# PCB_Plate_v6.net
KiCad netlist of a schematic drawn in EAGLE
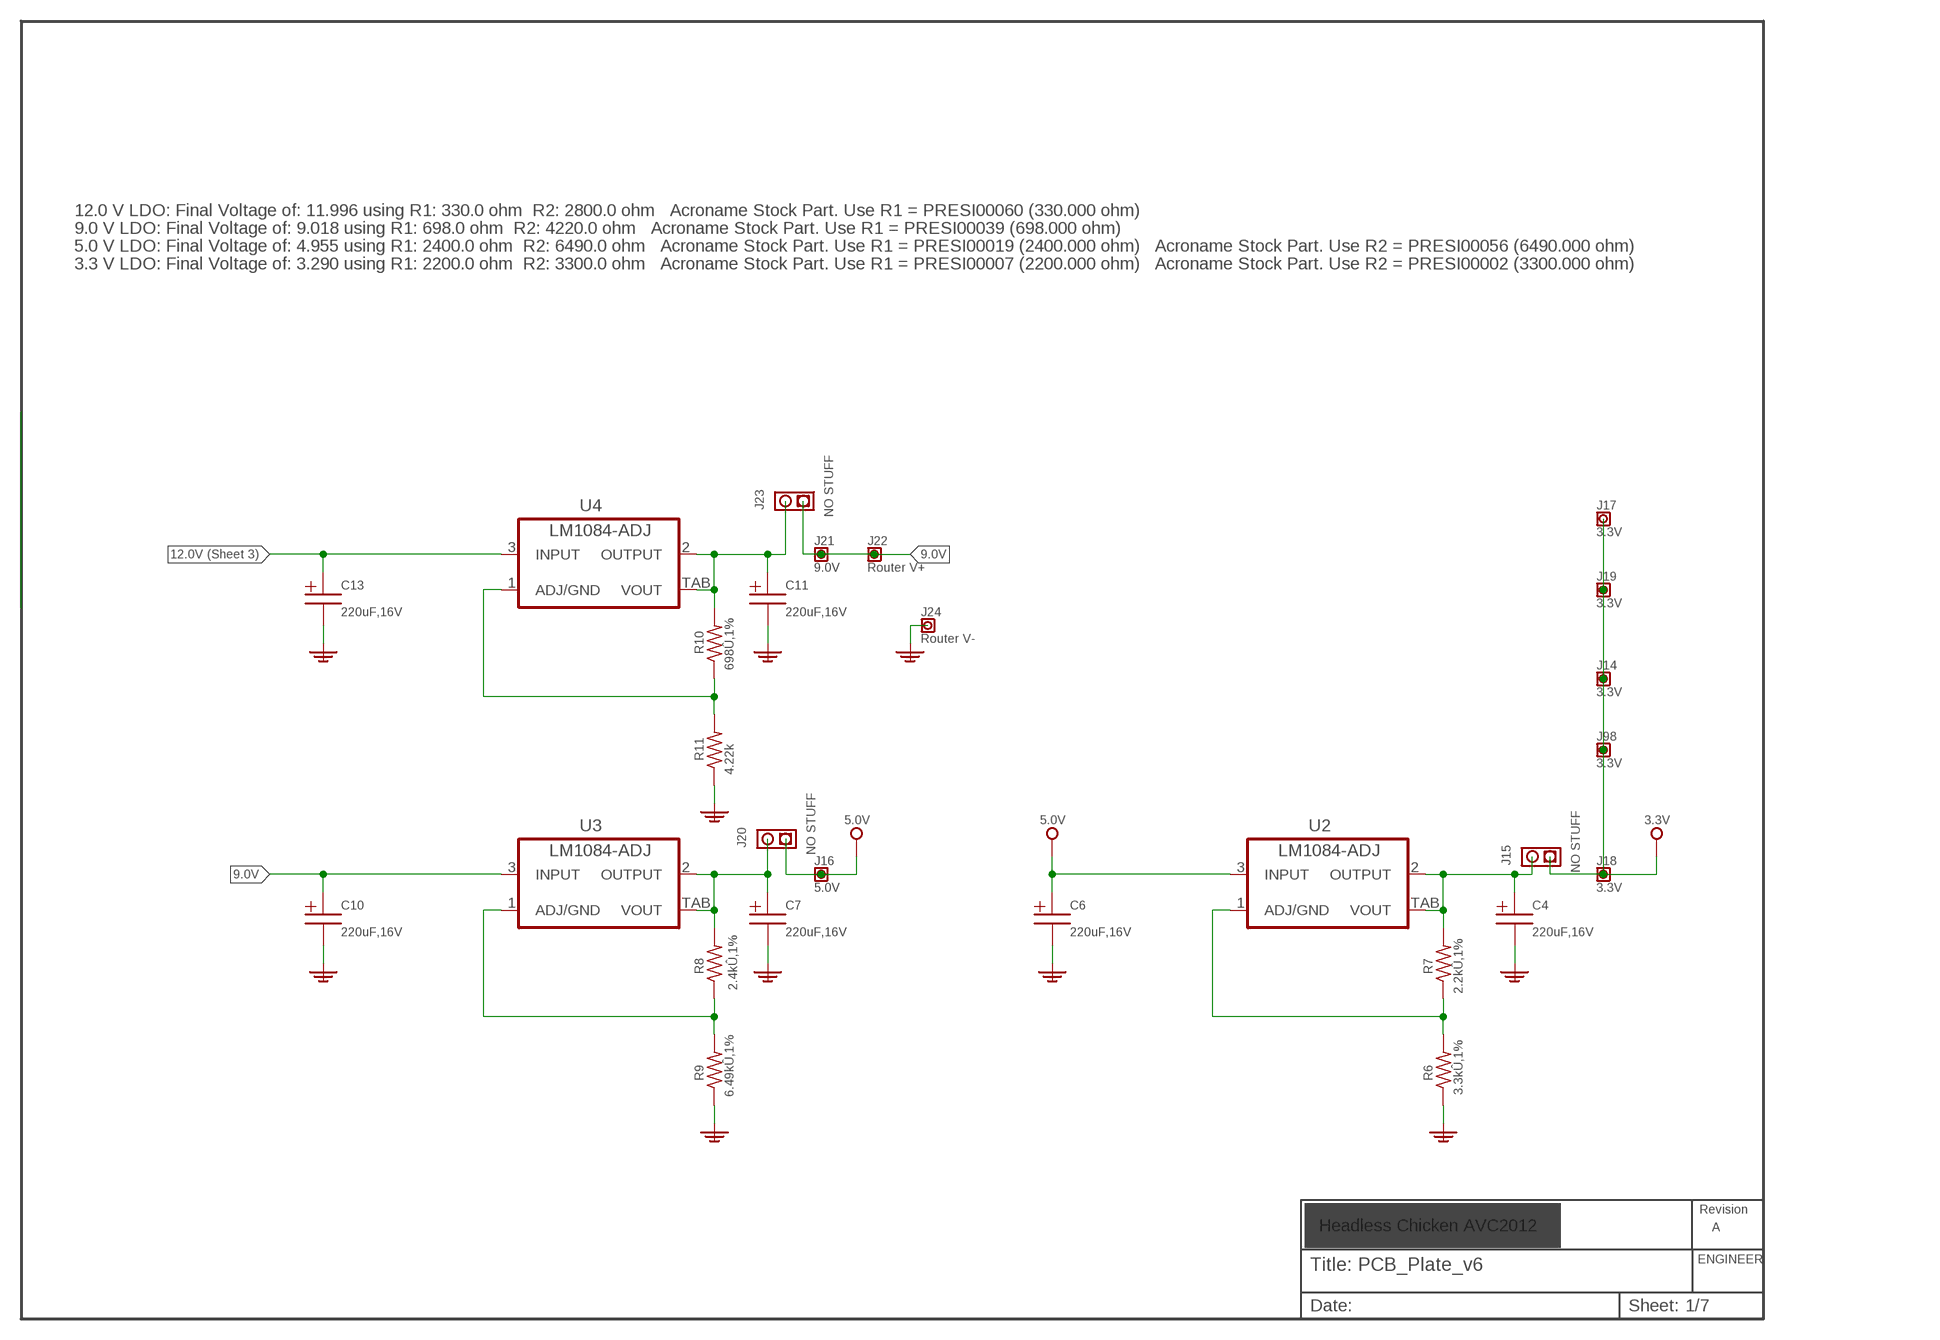
[diagram p0: schematic, sheet 1]
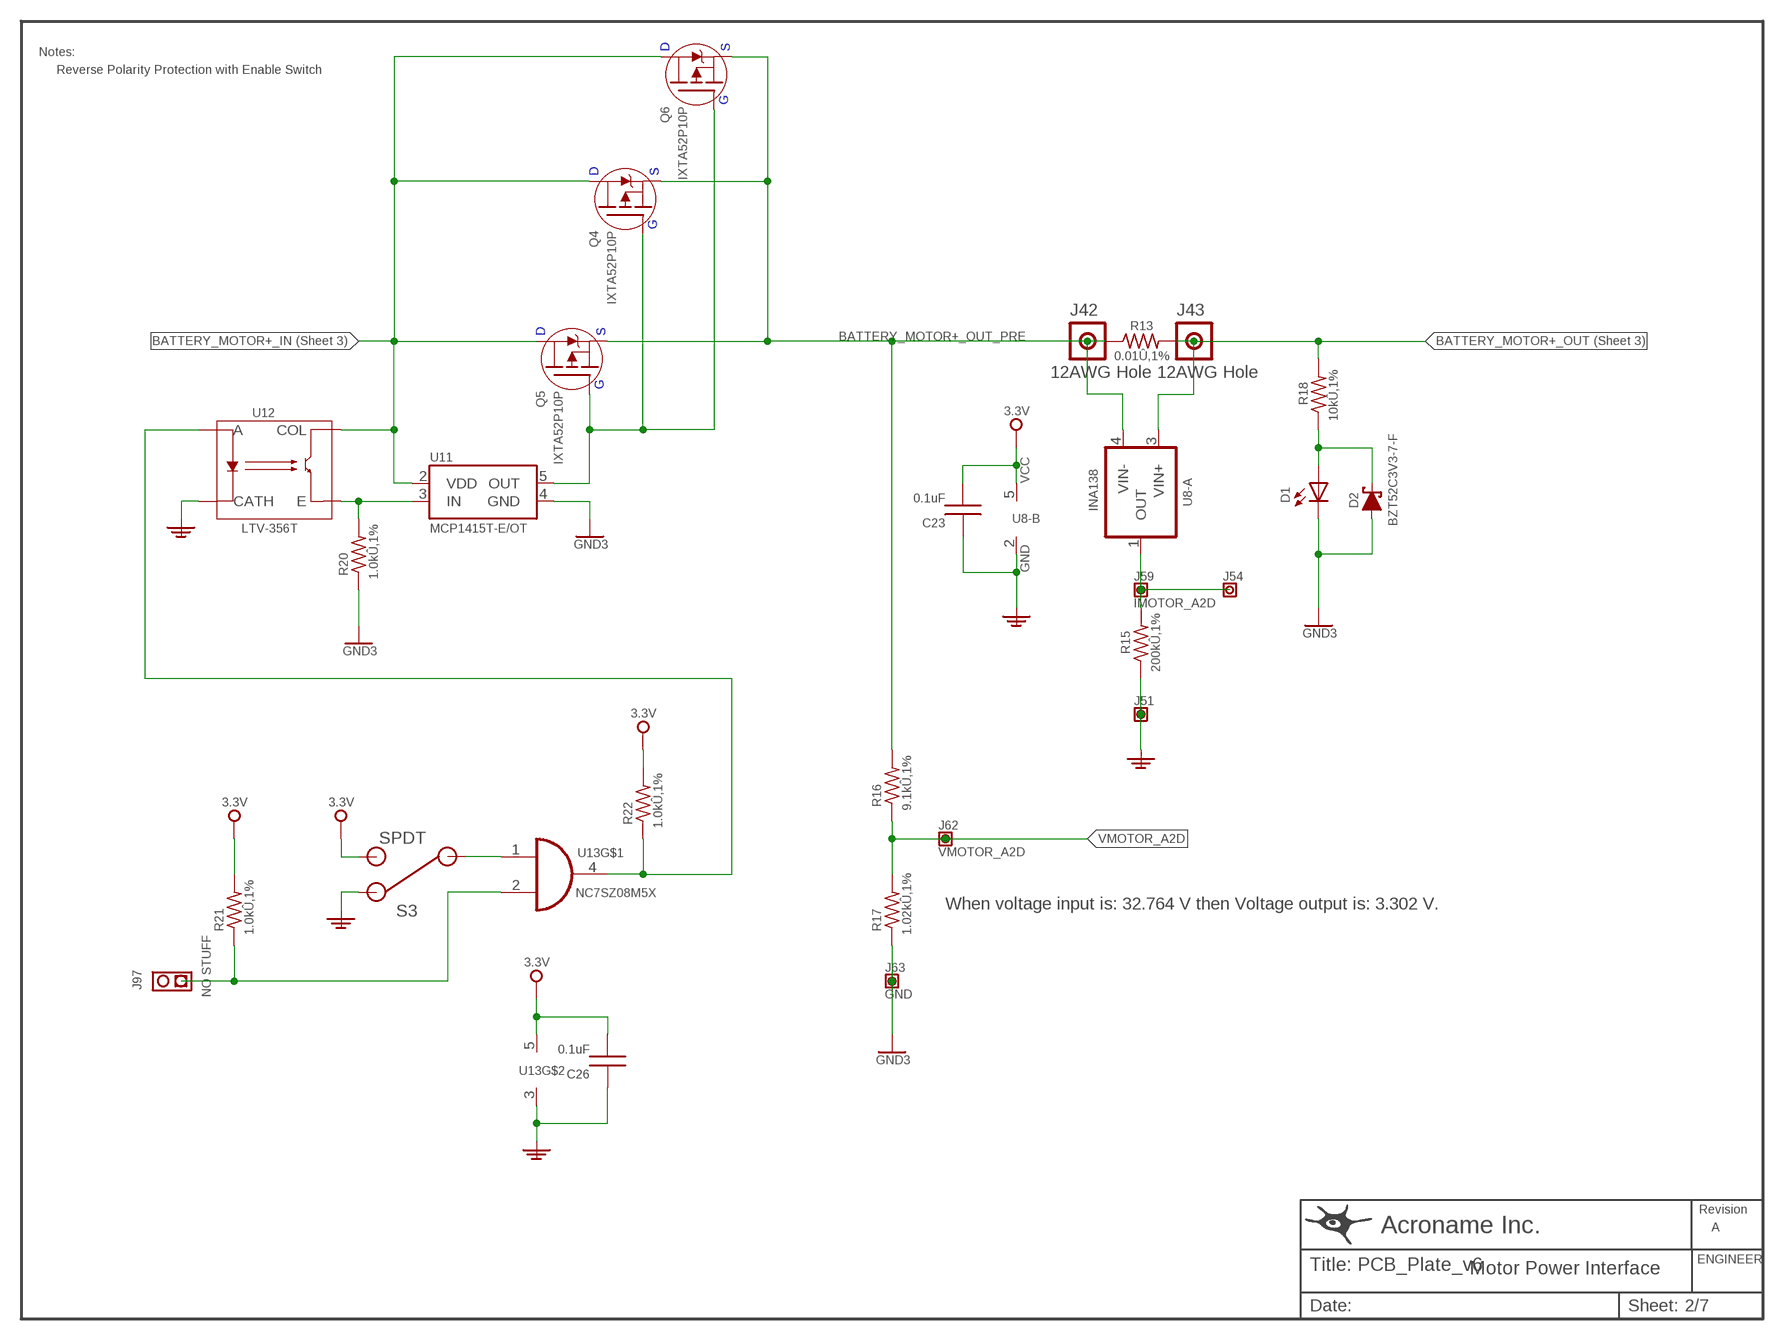
[diagram p1: schematic, sheet 2]
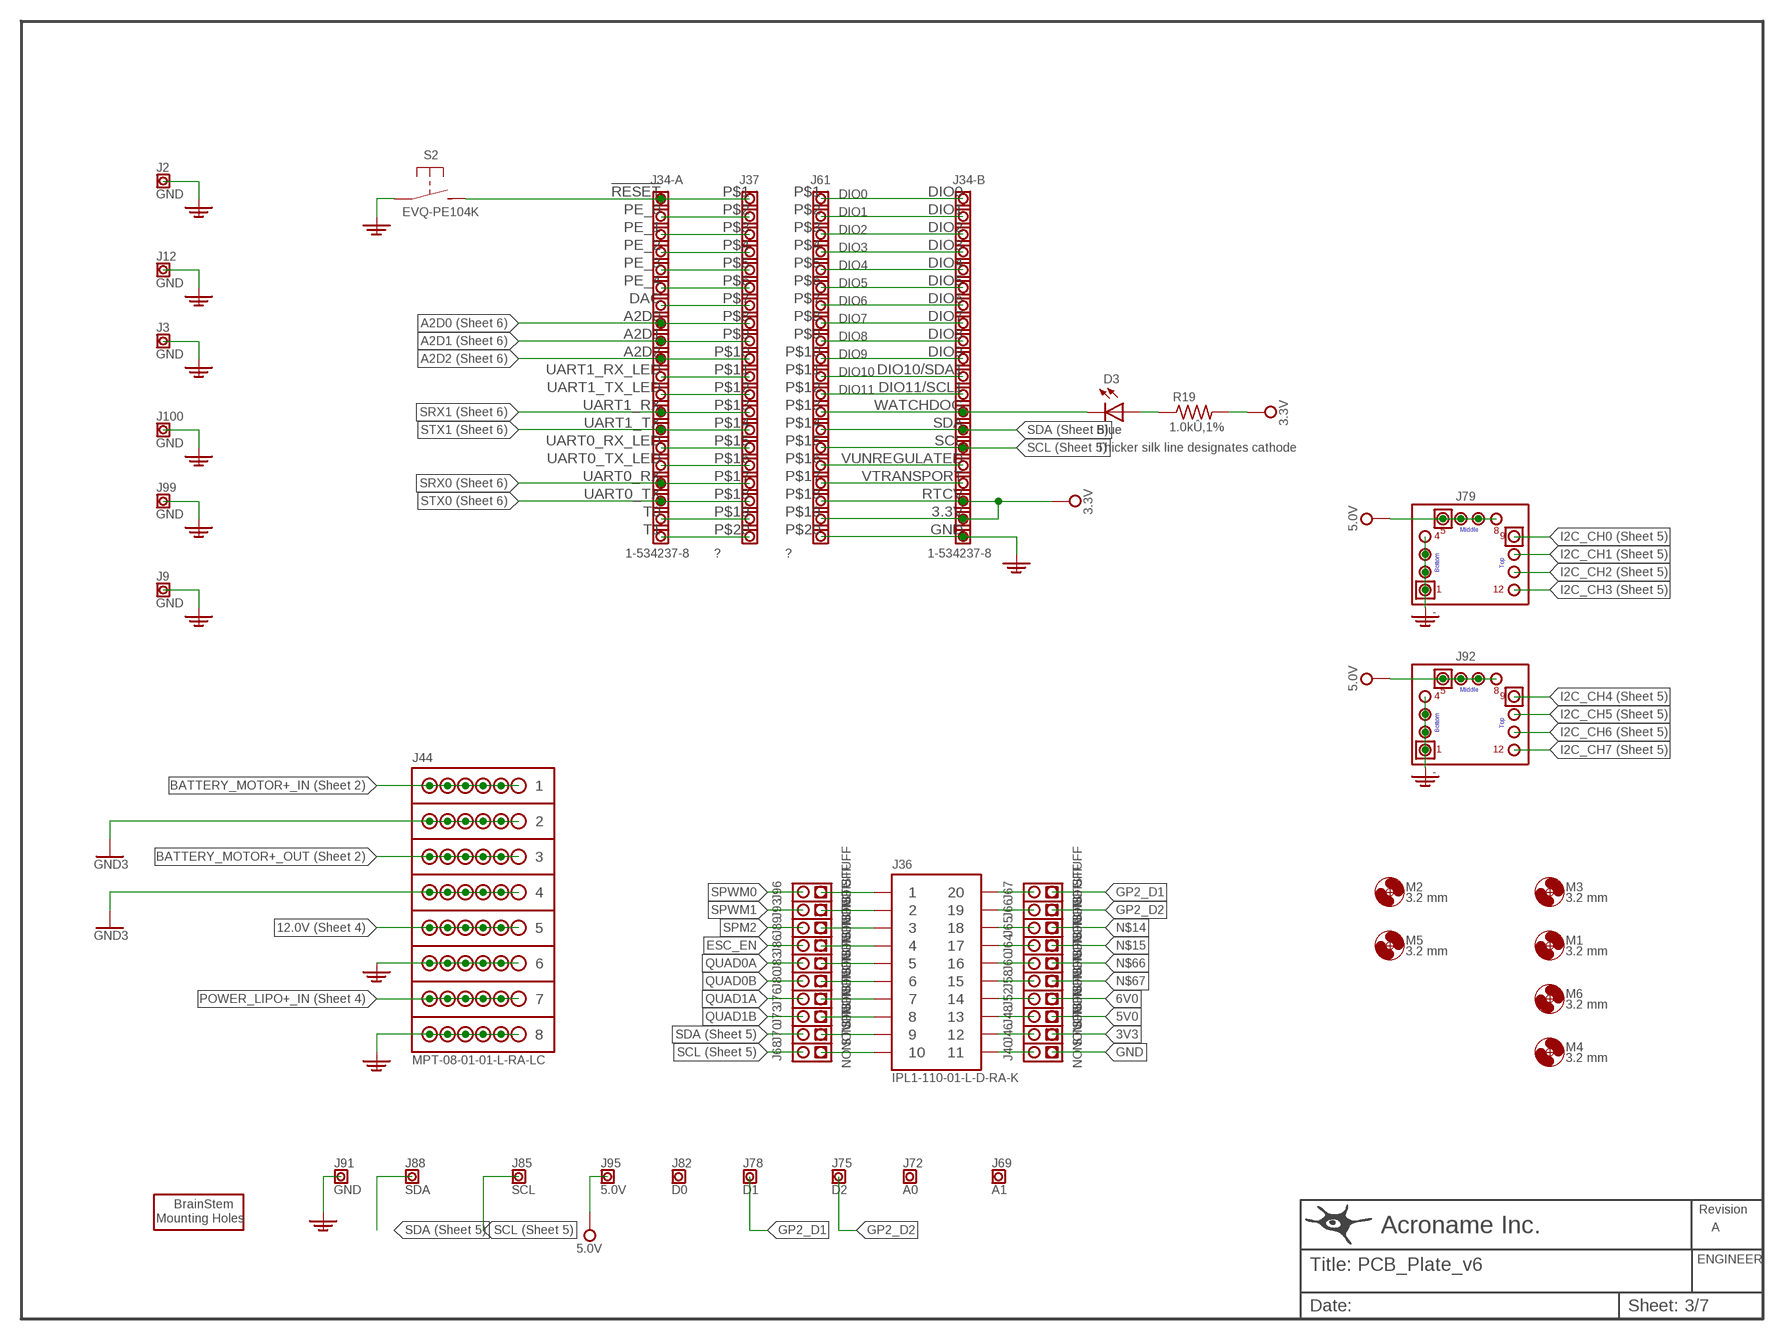
[diagram p2: schematic, sheet 3]
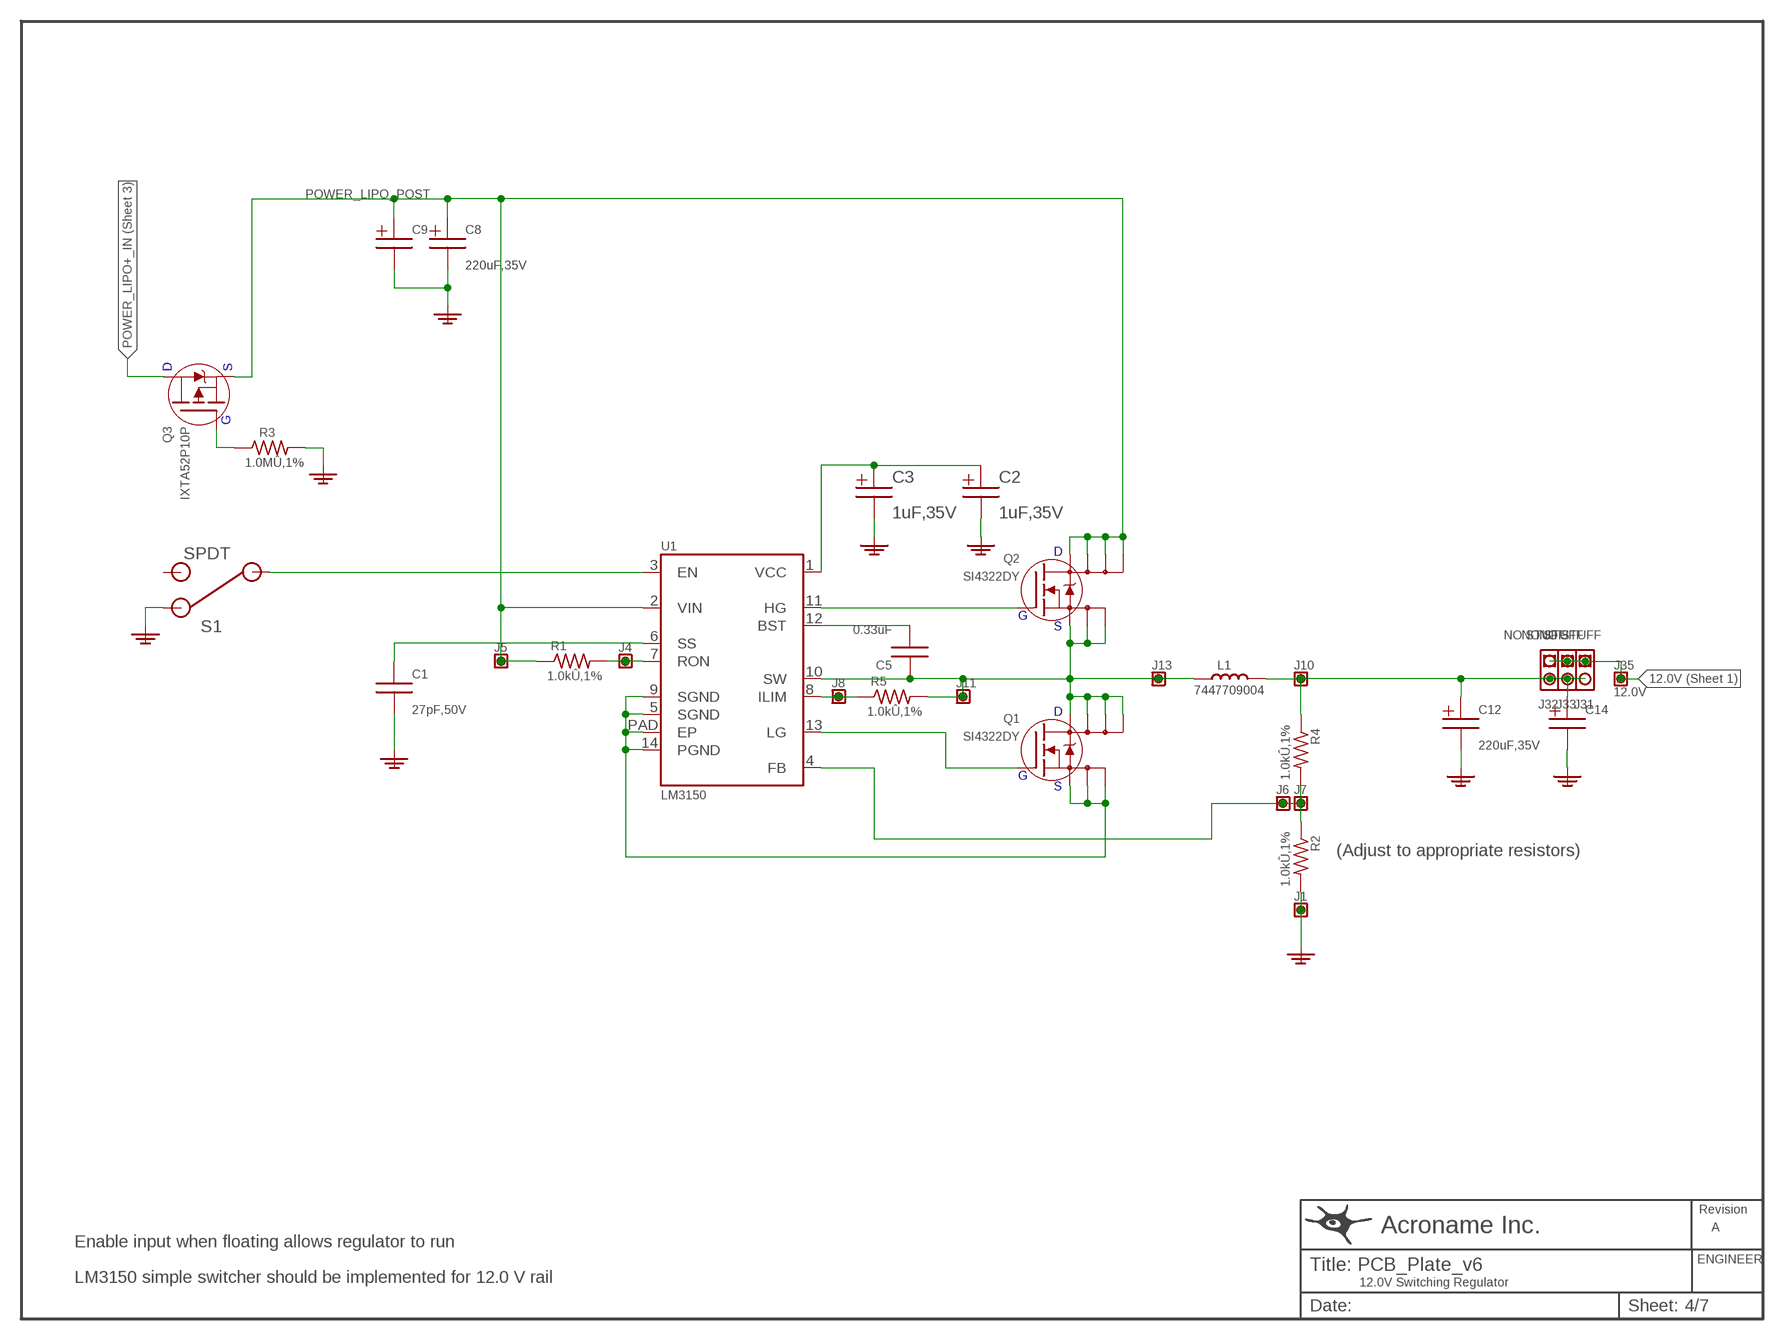
[diagram p3: schematic, sheet 4]
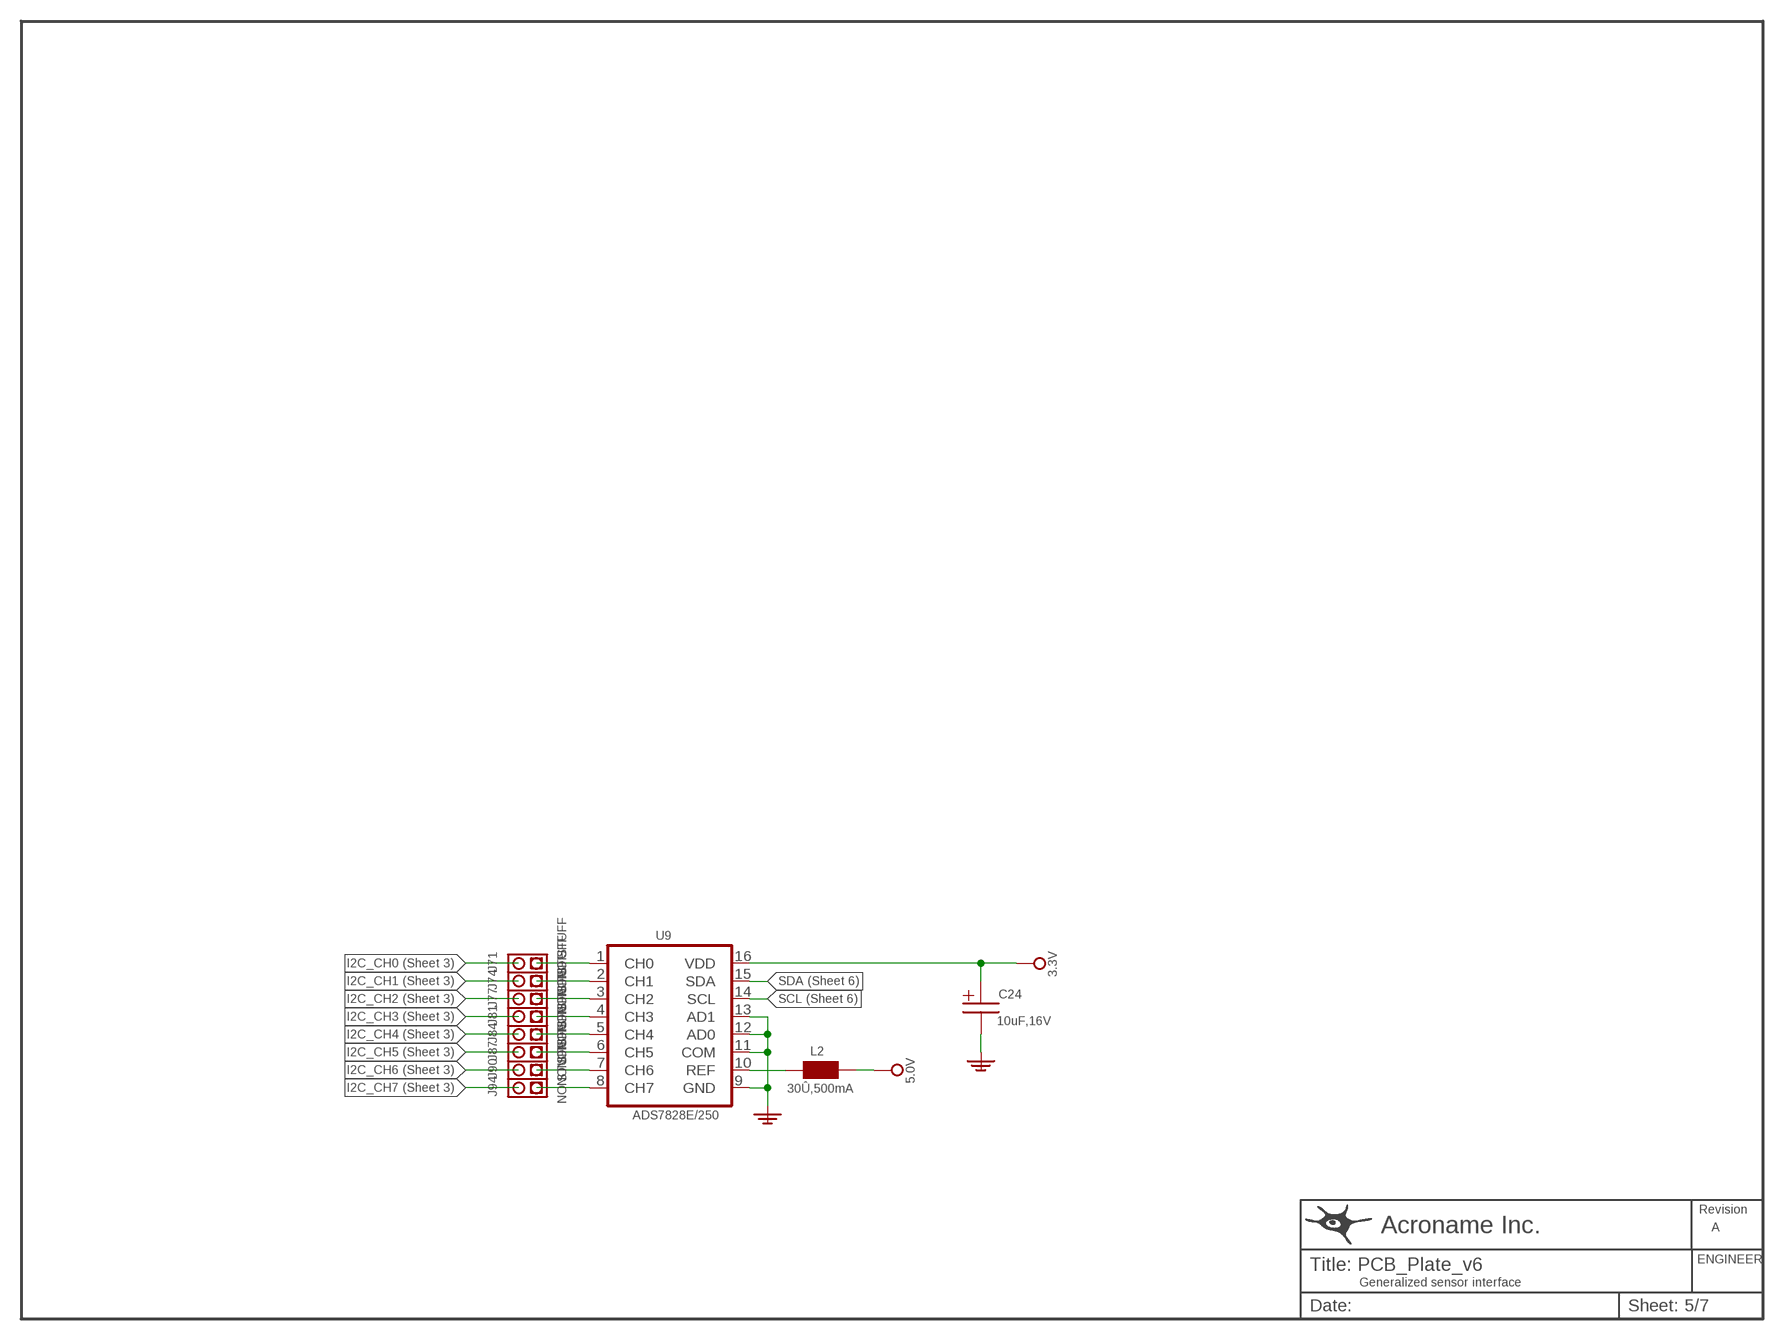
[diagram p4: schematic, sheet 5]
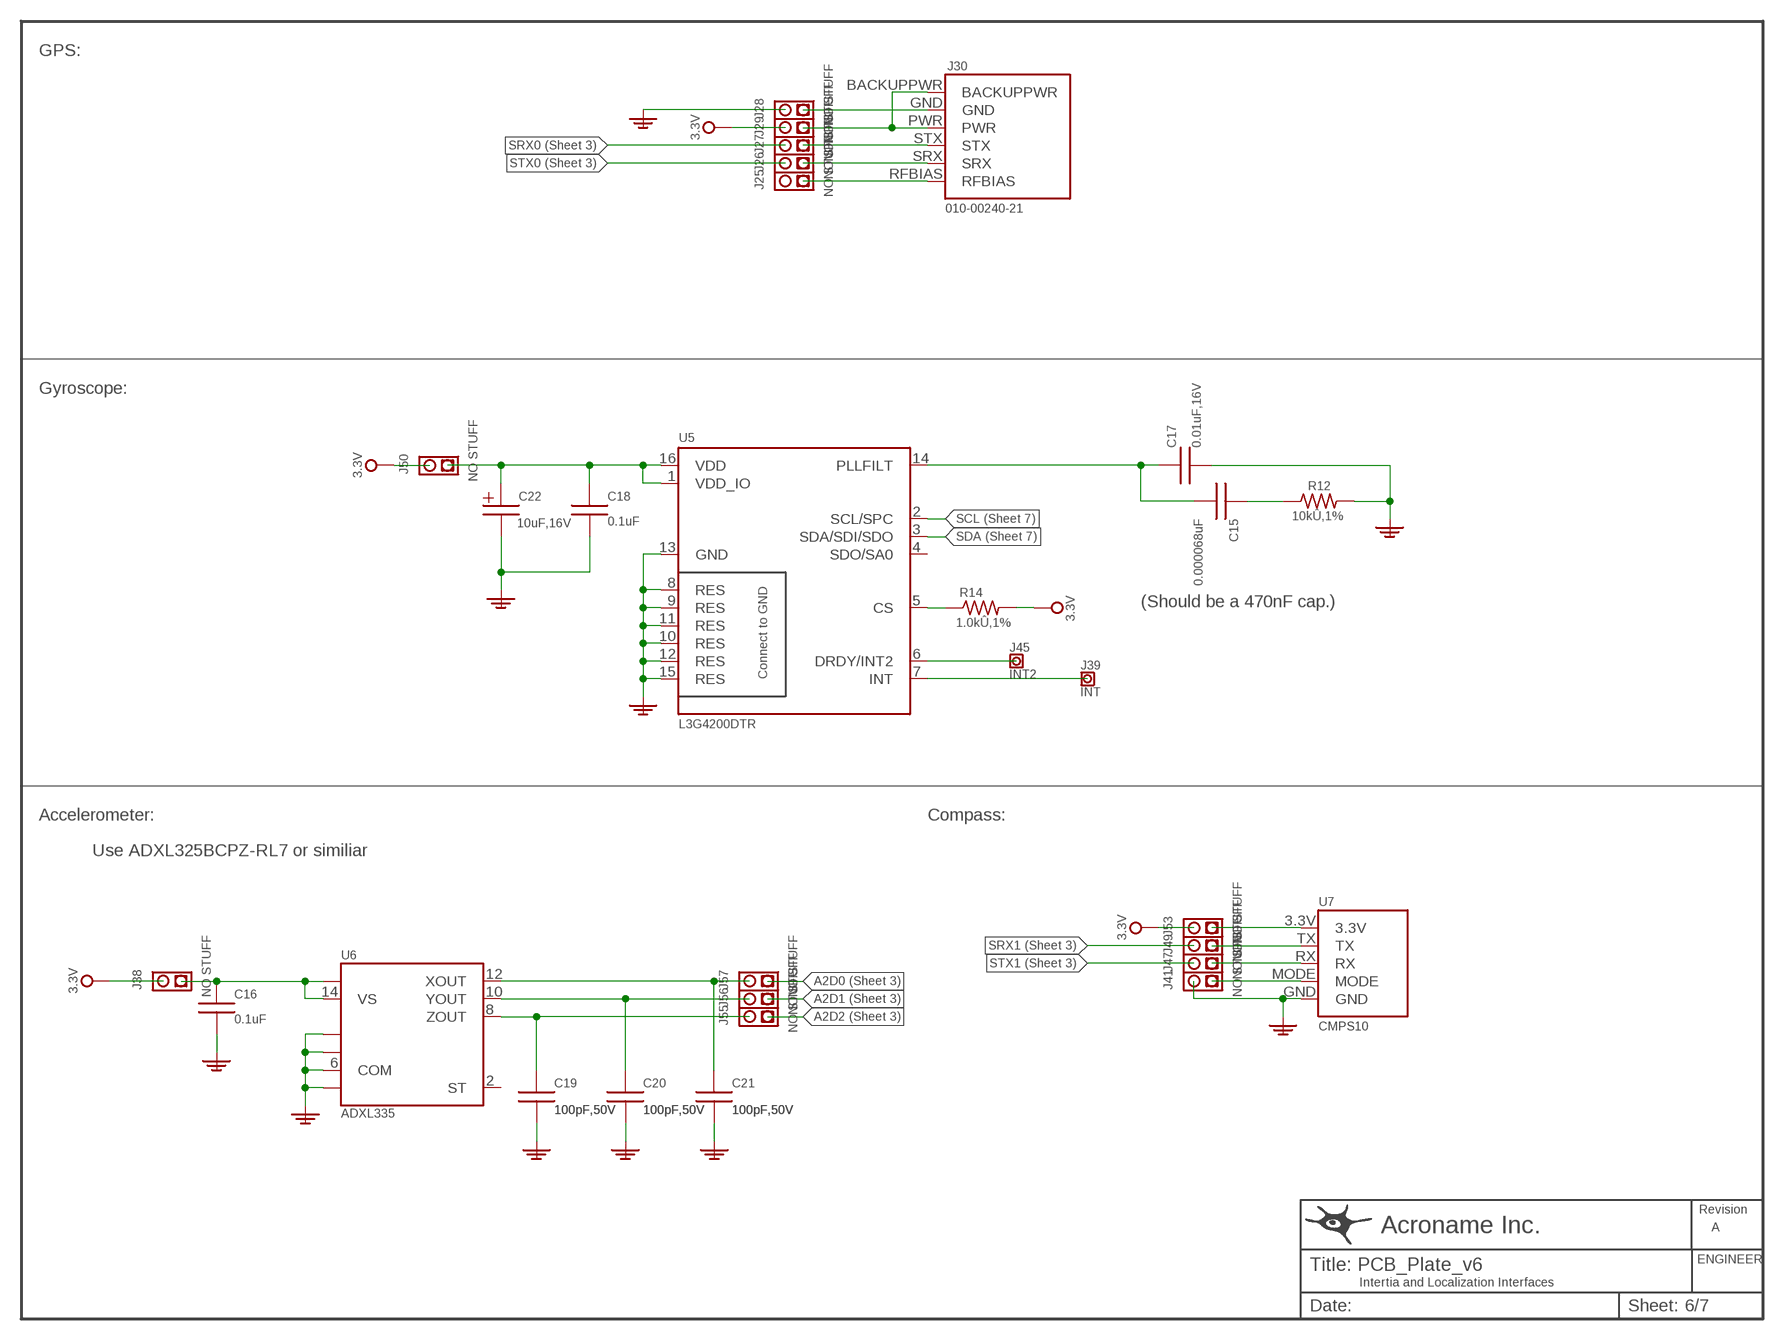
[diagram p5: schematic, sheet 6]
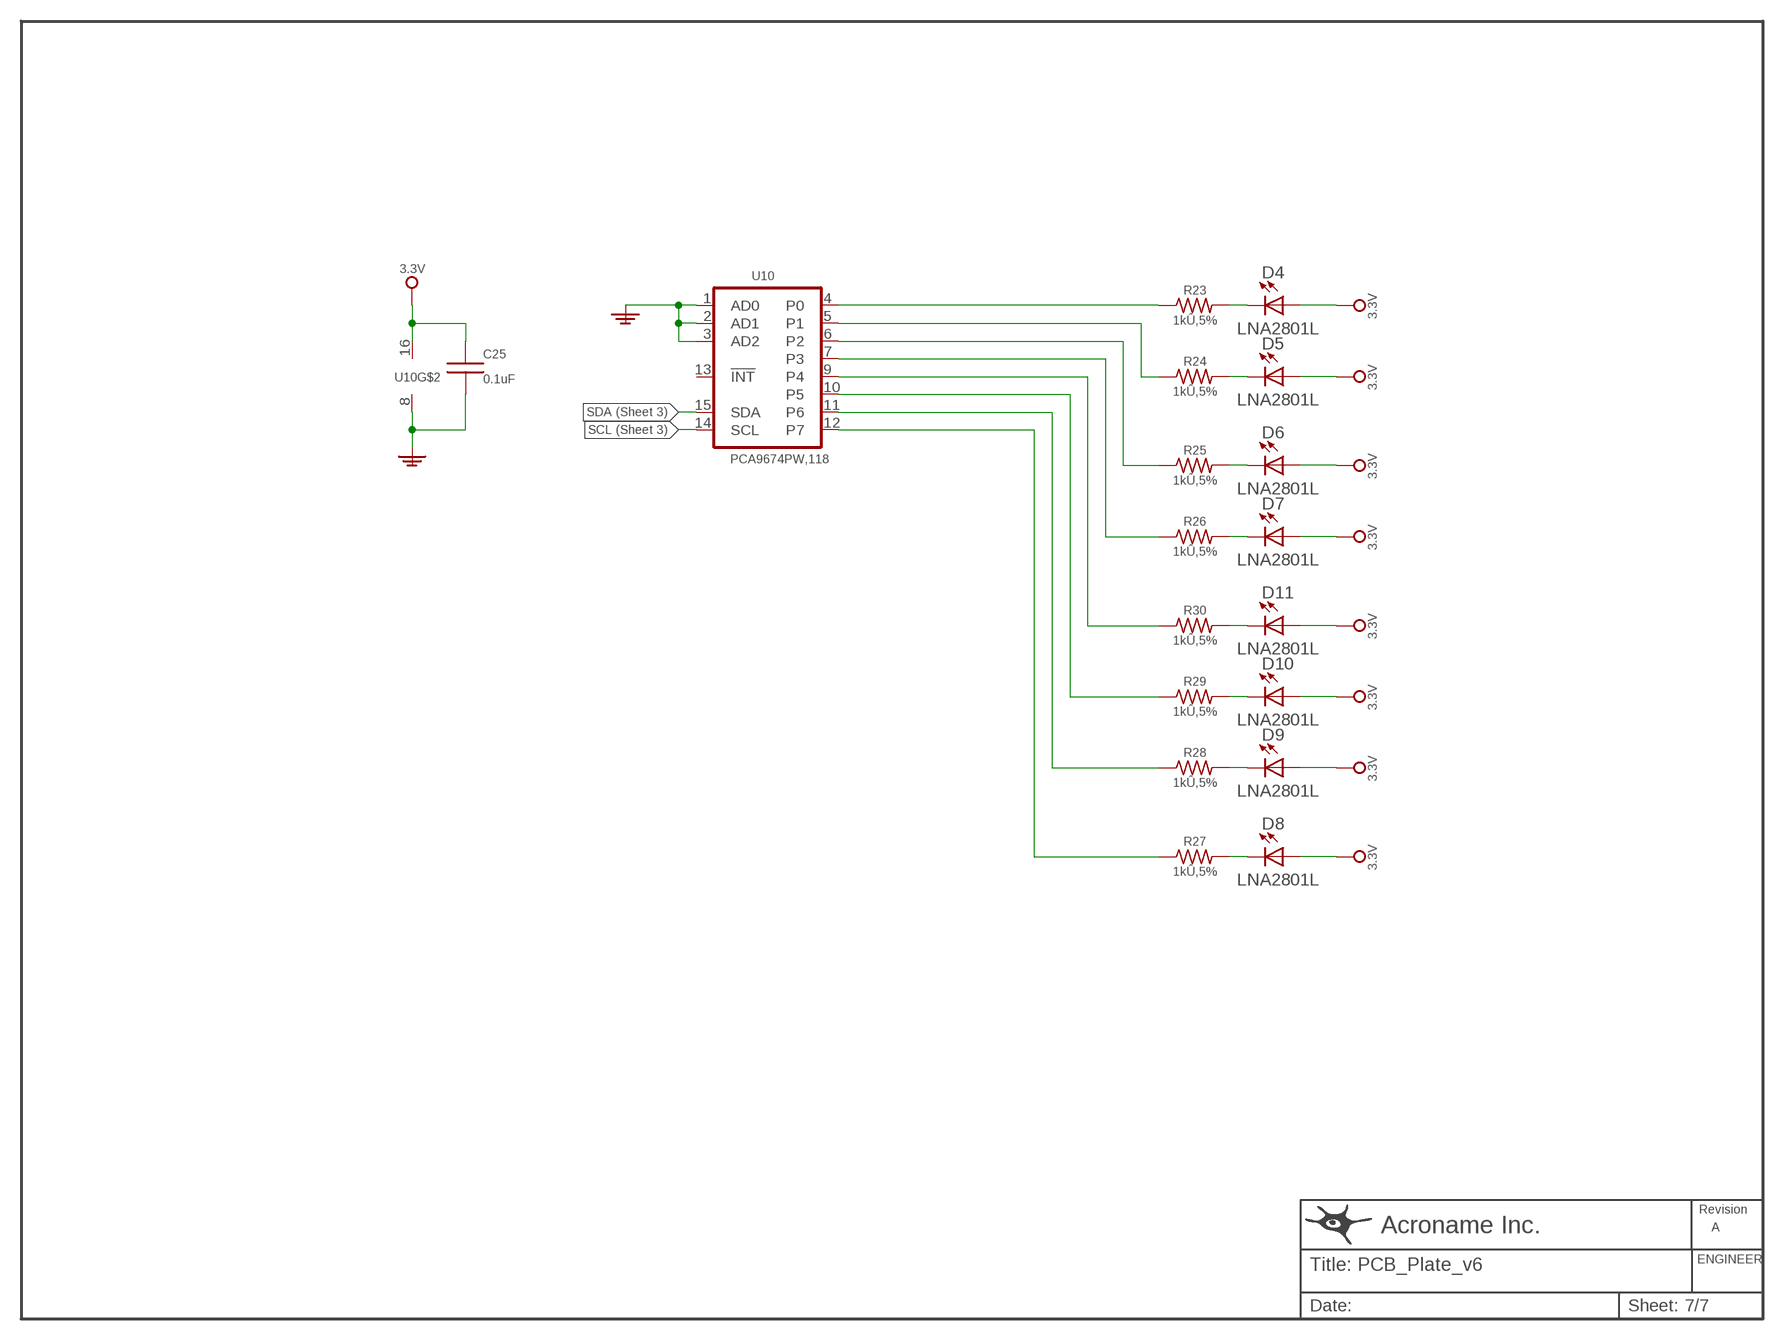
[diagram p6: schematic, sheet 7]

(export (version "E")
  (design (tool "Eeschema 10.0.6"))
  (components
    (comp (ref "C23")
      (value "PCAPI00015")
      (footprint "eagle-import:C0603")
      (fields (field (name "PARTNUM") "ECJ-1VB1E104K"))
      (libsource (lib "eagle-import") (part "PCAPI00015"))
    )
    (comp (ref "C26")
      (value "PCAPI00015")
      (footprint "eagle-import:C0603")
      (fields
        (field (name "PARTNUM") "ECJ-1VB1E104K")
        (field (name "ACRONAME") "PCAPI00015")
        (field (name "PARTNUM_1") "ECJ-1VB1E104K")
      )
      (libsource (lib "eagle-import") (part "PCAPI00015"))
    )
    (comp (ref "D1")
      (value "PDIOD00001")
      (footprint "eagle-import:CHIPLED_0805")
      (fields (field (name "PARTNUM") "LTST-C171CKT"))
      (libsource (lib "eagle-import") (part "PDIOD00001"))
    )
    (comp (ref "D2")
      (value "BZT52C3V3-7-F")
      (footprint "eagle-import:SOD123")
      (libsource (lib "eagle-import") (part "BZT52C3V3-7-F"))
    )
    (comp (ref "J42")
      (value "BOARD00008")
      (footprint "eagle-import:TSW1X1_12AWG")
      (libsource (lib "eagle-import") (part "BOARD00008"))
    )
    (comp (ref "J43")
      (value "BOARD00008")
      (footprint "eagle-import:TSW1X1_12AWG")
      (libsource (lib "eagle-import") (part "BOARD00008"))
    )
    (comp (ref "J51")
      (value "BOARD00003WVALUE")
      (footprint "eagle-import:TSW1X1_VAL")
      (libsource (lib "eagle-import") (part "BOARD00003WVALUE"))
    )
    (comp (ref "J54")
      (value "BOARD00003WVALUE")
      (footprint "eagle-import:TSW1X1_VAL")
      (libsource (lib "eagle-import") (part "BOARD00003WVALUE"))
    )
    (comp (ref "J59")
      (value "IMOTOR_A2D")
      (footprint "eagle-import:TSW1X1_VAL")
      (libsource (lib "eagle-import") (part "BOARD00003WVALUE"))
    )
    (comp (ref "J62")
      (value "VMOTOR_A2D")
      (footprint "eagle-import:TSW1X1_VAL")
      (libsource (lib "eagle-import") (part "BOARD00003WVALUE"))
    )
    (comp (ref "J63")
      (value "GND")
      (footprint "eagle-import:TSW1X1_VAL")
      (libsource (lib "eagle-import") (part "BOARD00003WVALUE"))
    )
    (comp (ref "J97")
      (value "BOARD00012")
      (footprint "eagle-import:TSW1X2")
      (libsource (lib "eagle-import") (part "BOARD00012"))
    )
    (comp (ref "Q4")
      (value "IXTA52P10P")
      (footprint "eagle-import:D2PACK")
      (fields (field (name "NOTES") "No Stuff"))
      (libsource (lib "eagle-import") (part "IXTA52P10P"))
    )
    (comp (ref "Q5")
      (value "IXTA52P10P")
      (footprint "eagle-import:D2PACK")
      (libsource (lib "eagle-import") (part "IXTA52P10P"))
    )
    (comp (ref "Q6")
      (value "IXTA52P10P")
      (footprint "eagle-import:D2PACK")
      (fields (field (name "NOTES") "No Stuff"))
      (libsource (lib "eagle-import") (part "IXTA52P10P"))
    )
    (comp (ref "R13")
      (value "PRESI00041")
      (footprint "eagle-import:R4527")
      (fields (field (name "PARTNUM") "WSR5R0100FEA"))
      (libsource (lib "eagle-import") (part "PRESI00041"))
    )
    (comp (ref "R15")
      (value "PRESI00018")
      (footprint "eagle-import:R0603")
      (libsource (lib "eagle-import") (part "PRESI00018"))
    )
    (comp (ref "R16")
      (value "ERJ-2RKF9101X")
      (footprint "eagle-import:R0402@1")
      (libsource (lib "eagle-import") (part "ERJ-2RKF9101X"))
    )
    (comp (ref "R17")
      (value "ERJ-2RKF1021X")
      (footprint "eagle-import:R0402@1")
      (libsource (lib "eagle-import") (part "ERJ-2RKF1021X"))
    )
    (comp (ref "R18")
      (value "PRESI00005")
      (footprint "eagle-import:R0603")
      (fields (field (name "PARTNUM") "ERJ-3EKF1002V"))
      (libsource (lib "eagle-import") (part "PRESI00005"))
    )
    (comp (ref "R20")
      (value "PRESI00006")
      (footprint "eagle-import:R0603")
      (fields
        (field (name "PARTNUM") "ERJ-3EKF1001V")
        (field (name "ACRONAME") "PRESI00006")
        (field (name "PARTNUM_1") "ERJ-3EKF1001V")
        (field (name "UNITCOST") "0.006")
      )
      (libsource (lib "eagle-import") (part "PRESI00006"))
    )
    (comp (ref "R21")
      (value "PRESI00006")
      (footprint "eagle-import:R0603")
      (fields
        (field (name "PARTNUM") "ERJ-3EKF1001V")
        (field (name "ACRONAME") "PRESI00006")
        (field (name "PARTNUM_1") "ERJ-3EKF1001V")
        (field (name "UNITCOST") "0.006")
      )
      (libsource (lib "eagle-import") (part "PRESI00006"))
    )
    (comp (ref "R22")
      (value "PRESI00006")
      (footprint "eagle-import:R0603")
      (fields (field (name "PARTNUM") "ERJ-3EKF1001V"))
      (libsource (lib "eagle-import") (part "PRESI00006"))
    )
    (comp (ref "S3")
      (value "PMISC00005")
      (footprint "eagle-import:SPDTRA")
      (fields (field (name "PARTNUM") "1101M2S3AQE2"))
      (libsource (lib "eagle-import") (part "PMISC00005"))
    )
    (comp (ref "U8")
      (value "PCHIP00026")
      (footprint "eagle-import:SOT23-5")
      (fields (field (name "PARTNUM") "INA168NA/250"))
      (libsource (lib "eagle-import") (part "PCHIP00026"))
    )
    (comp (ref "U11")
      (value "MCP1416")
      (footprint "eagle-import:SOT23-5")
      (fields (field (name "PARTNUM") "MCP1416T-E/OT") (field (name "PARTNUM_1") "MCP1415T-E/OT"))
      (libsource (lib "eagle-import") (part "MCP1416"))
    )
    (comp (ref "U12")
      (value "LTV-356T")
      (footprint "eagle-import:4-SMD")
      (libsource (lib "eagle-import") (part "LTV-356T"))
    )
    (comp (ref "U13")
      (value "NC7SZ08M5X")
      (footprint "eagle-import:SOT23-5")
      (libsource (lib "eagle-import") (part "NC7SZ08M5X"))
    )
    (comp (ref "C25")
      (value "PCAPI00015")
      (footprint "eagle-import:C0603")
      (fields (field (name "PARTNUM") "ECJ-1VB1E104K"))
      (libsource (lib "eagle-import") (part "PCAPI00015"))
    )
    (comp (ref "D4")
      (value "PDIOD00003")
      (footprint "eagle-import:LT3LR1N02-001")
      (libsource (lib "eagle-import") (part "PDIOD00003"))
    )
    (comp (ref "D5")
      (value "PDIOD00003")
      (footprint "eagle-import:LT3LR1N02-001")
      (libsource (lib "eagle-import") (part "PDIOD00003"))
    )
    (comp (ref "D6")
      (value "PDIOD00003")
      (footprint "eagle-import:LT3LR1N02-001")
      (libsource (lib "eagle-import") (part "PDIOD00003"))
    )
    (comp (ref "D7")
      (value "PDIOD00003")
      (footprint "eagle-import:LT3LR1N02-001")
      (libsource (lib "eagle-import") (part "PDIOD00003"))
    )
    (comp (ref "D8")
      (value "PDIOD00003")
      (footprint "eagle-import:LT3LR1N02-001")
      (libsource (lib "eagle-import") (part "PDIOD00003"))
    )
    (comp (ref "D9")
      (value "PDIOD00003")
      (footprint "eagle-import:LT3LR1N02-001")
      (libsource (lib "eagle-import") (part "PDIOD00003"))
    )
    (comp (ref "D10")
      (value "PDIOD00003")
      (footprint "eagle-import:LT3LR1N02-001")
      (libsource (lib "eagle-import") (part "PDIOD00003"))
    )
    (comp (ref "D11")
      (value "PDIOD00003")
      (footprint "eagle-import:LT3LR1N02-001")
      (libsource (lib "eagle-import") (part "PDIOD00003"))
    )
    (comp (ref "R23")
      (value "PRESI00012")
      (footprint "eagle-import:CFR-12")
      (fields (field (name "PARTNUM") "?"))
      (libsource (lib "eagle-import") (part "PRESI00012"))
    )
    (comp (ref "R24")
      (value "PRESI00012")
      (footprint "eagle-import:CFR-12")
      (fields (field (name "PARTNUM") "?"))
      (libsource (lib "eagle-import") (part "PRESI00012"))
    )
    (comp (ref "R25")
      (value "PRESI00012")
      (footprint "eagle-import:CFR-12")
      (fields (field (name "PARTNUM") "?"))
      (libsource (lib "eagle-import") (part "PRESI00012"))
    )
    (comp (ref "R26")
      (value "PRESI00012")
      (footprint "eagle-import:CFR-12")
      (fields (field (name "PARTNUM") "?"))
      (libsource (lib "eagle-import") (part "PRESI00012"))
    )
    (comp (ref "R27")
      (value "PRESI00012")
      (footprint "eagle-import:CFR-12")
      (fields (field (name "PARTNUM") "?"))
      (libsource (lib "eagle-import") (part "PRESI00012"))
    )
    (comp (ref "R28")
      (value "PRESI00012")
      (footprint "eagle-import:CFR-12")
      (fields (field (name "PARTNUM") "?"))
      (libsource (lib "eagle-import") (part "PRESI00012"))
    )
    (comp (ref "R29")
      (value "PRESI00012")
      (footprint "eagle-import:CFR-12")
      (fields (field (name "PARTNUM") "?"))
      (libsource (lib "eagle-import") (part "PRESI00012"))
    )
    (comp (ref "R30")
      (value "PRESI00012")
      (footprint "eagle-import:CFR-12")
      (fields (field (name "PARTNUM") "?"))
      (libsource (lib "eagle-import") (part "PRESI00012"))
    )
    (comp (ref "U10")
      (value "I2C_DIO_EXPANDER")
      (footprint "eagle-import:TSSOP16")
      (fields (field (name "PARTNUM") "PCA9674PW,118"))
      (libsource (lib "eagle-import") (part "I2C_DIO_EXPANDER"))
    )
    (comp (ref "C15")
      (value "PCAPI00023")
      (footprint "eagle-import:C0603")
      (libsource (lib "eagle-import") (part "PCAPI00023"))
    )
    (comp (ref "C16")
      (value "PCAPI00015")
      (footprint "eagle-import:C0603")
      (fields (field (name "PARTNUM") "ECJ-1VB1E104K"))
      (libsource (lib "eagle-import") (part "PCAPI00015"))
    )
    (comp (ref "C17")
      (value "PCAPI00007")
      (footprint "eagle-import:C0603")
      (fields (field (name "PARTNUM") "ECJ-1VB1C103K"))
      (libsource (lib "eagle-import") (part "PCAPI00007"))
    )
    (comp (ref "C18")
      (value "PCAPI00015")
      (footprint "eagle-import:C0603")
      (fields (field (name "PARTNUM") "ECJ-1VB1E104K"))
      (libsource (lib "eagle-import") (part "PCAPI00015"))
    )
    (comp (ref "C19")
      (value "PCAPI00016")
      (footprint "eagle-import:C0603")
      (fields (field (name "PARTNUM") "ECJ-1VC1H101J"))
      (libsource (lib "eagle-import") (part "PCAPI00016"))
    )
    (comp (ref "C20")
      (value "PCAPI00016")
      (footprint "eagle-import:C0603")
      (fields (field (name "PARTNUM") "ECJ-1VC1H101J"))
      (libsource (lib "eagle-import") (part "PCAPI00016"))
    )
    (comp (ref "C21")
      (value "PCAPI00016")
      (footprint "eagle-import:C0603")
      (fields (field (name "PARTNUM") "ECJ-1VC1H101J"))
      (libsource (lib "eagle-import") (part "PCAPI00016"))
    )
    (comp (ref "C22")
      (value "T491A106K010AT")
      (footprint "eagle-import:SMC_A")
      (fields (field (name "PARTNUM") "T491A106M016AT"))
      (libsource (lib "eagle-import") (part "T491A106K010AT"))
    )
    (comp (ref "J25")
      (value "BOARD00012")
      (footprint "eagle-import:TSW1X2")
      (libsource (lib "eagle-import") (part "BOARD00012"))
    )
    (comp (ref "J26")
      (value "BOARD00012")
      (footprint "eagle-import:TSW1X2")
      (libsource (lib "eagle-import") (part "BOARD00012"))
    )
    (comp (ref "J27")
      (value "BOARD00012")
      (footprint "eagle-import:TSW1X2")
      (libsource (lib "eagle-import") (part "BOARD00012"))
    )
    (comp (ref "J28")
      (value "BOARD00012")
      (footprint "eagle-import:TSW1X2")
      (libsource (lib "eagle-import") (part "BOARD00012"))
    )
    (comp (ref "J29")
      (value "BOARD00012")
      (footprint "eagle-import:TSW1X2")
      (libsource (lib "eagle-import") (part "BOARD00012"))
    )
    (comp (ref "J30")
      (value "GPS15X")
      (footprint "eagle-import:GPS15")
      (fields (field (name "PARTNUM") "010-00240-21 "))
      (libsource (lib "eagle-import") (part "GPS15X"))
    )
    (comp (ref "J38")
      (value "BOARD00012")
      (footprint "eagle-import:TSW1X2")
      (libsource (lib "eagle-import") (part "BOARD00012"))
    )
    (comp (ref "J39")
      (value "INT")
      (footprint "eagle-import:TSW1X1_VAL")
      (libsource (lib "eagle-import") (part "BOARD00003WVALUE"))
    )
    (comp (ref "J41")
      (value "BOARD00012")
      (footprint "eagle-import:TSW1X2")
      (libsource (lib "eagle-import") (part "BOARD00012"))
    )
    (comp (ref "J45")
      (value "INT2")
      (footprint "eagle-import:TSW1X1_VAL")
      (libsource (lib "eagle-import") (part "BOARD00003WVALUE"))
    )
    (comp (ref "J47")
      (value "BOARD00012")
      (footprint "eagle-import:TSW1X2")
      (libsource (lib "eagle-import") (part "BOARD00012"))
    )
    (comp (ref "J49")
      (value "BOARD00012")
      (footprint "eagle-import:TSW1X2")
      (libsource (lib "eagle-import") (part "BOARD00012"))
    )
    (comp (ref "J50")
      (value "BOARD00012")
      (footprint "eagle-import:TSW1X2")
      (libsource (lib "eagle-import") (part "BOARD00012"))
    )
    (comp (ref "J53")
      (value "BOARD00012")
      (footprint "eagle-import:TSW1X2")
      (libsource (lib "eagle-import") (part "BOARD00012"))
    )
    (comp (ref "J55")
      (value "BOARD00012")
      (footprint "eagle-import:TSW1X2")
      (libsource (lib "eagle-import") (part "BOARD00012"))
    )
    (comp (ref "J56")
      (value "BOARD00012")
      (footprint "eagle-import:TSW1X2")
      (libsource (lib "eagle-import") (part "BOARD00012"))
    )
    (comp (ref "J57")
      (value "BOARD00012")
      (footprint "eagle-import:TSW1X2")
      (libsource (lib "eagle-import") (part "BOARD00012"))
    )
    (comp (ref "R12")
      (value "PRESI00005")
      (footprint "eagle-import:R0603")
      (fields (field (name "PARTNUM") "ERJ-3EKF1002V"))
      (libsource (lib "eagle-import") (part "PRESI00005"))
    )
    (comp (ref "R14")
      (value "PRESI00006")
      (footprint "eagle-import:R0603")
      (fields (field (name "PARTNUM") "ERJ-3EKF1001V"))
      (libsource (lib "eagle-import") (part "PRESI00006"))
    )
    (comp (ref "U5")
      (value "L3G4200DTR")
      (footprint "eagle-import:LGA16")
      (libsource (lib "eagle-import") (part "L3G4200DTR"))
    )
    (comp (ref "U6")
      (value "ADXL335")
      (footprint "eagle-import:LFCSP-16")
      (libsource (lib "eagle-import") (part "ADXL335"))
    )
    (comp (ref "U7")
      (value "CMPS10")
      (footprint "eagle-import:CMPS10")
      (libsource (lib "eagle-import") (part "CMPS10"))
    )
    (comp (ref "D3")
      (value "LTST-C171TBKT")
      (footprint "eagle-import:CHIPLED_0805")
      (libsource (lib "eagle-import") (part "LTST-C171TBKT"))
    )
    (comp (ref "J2")
      (value "GND")
      (footprint "eagle-import:TSW1X1_VAL")
      (fields (field (name "ACRONAME") "-") (field (name "PARTNUM") "-") (field (name "UNITCOST") "0.0"))
      (libsource (lib "eagle-import") (part "BOARD00003WVALUE"))
    )
    (comp (ref "J3")
      (value "GND")
      (footprint "eagle-import:TSW1X1_VAL")
      (fields (field (name "ACRONAME") "-") (field (name "PARTNUM") "-") (field (name "UNITCOST") "0.0"))
      (libsource (lib "eagle-import") (part "BOARD00003WVALUE"))
    )
    (comp (ref "J9")
      (value "GND")
      (footprint "eagle-import:TSW1X1_VAL")
      (fields (field (name "ACRONAME") "-") (field (name "PARTNUM") "-") (field (name "UNITCOST") "0.0"))
      (libsource (lib "eagle-import") (part "BOARD00003WVALUE"))
    )
    (comp (ref "J12")
      (value "GND")
      (footprint "eagle-import:TSW1X1_VAL")
      (fields (field (name "ACRONAME") "-") (field (name "PARTNUM") "-") (field (name "UNITCOST") "0.0"))
      (libsource (lib "eagle-import") (part "BOARD00003WVALUE"))
    )
    (comp (ref "J34")
      (value "BRAINSTEMSOCKET_FEMALE")
      (footprint "eagle-import:BRAINSTEMSOCKET")
      (fields
        (field (name "PARTNUM") "1-534237-8")
        (field (name "ALTERNATIVE") "SSW-120-01-G-S:75915-320LF")
        (field (name "PARTNUM_1") "1-534237-8")
      )
      (libsource (lib "eagle-import") (part "BRAINSTEMSOCKET_FEMALE"))
    )
    (comp (ref "J36")
      (value "IPL1-1XX-02-XXX-DH-K-XX-MKT")
      (footprint "eagle-import:IPL1-110-01-S-RA")
      (fields (field (name "PARTNUM") "IPL1-110-01-L-D-RA-K"))
      (libsource (lib "eagle-import") (part "IPL1-1XX-02-XXX-DH-K-XX-MKT"))
    )
    (comp (ref "J37")
      (value "TSW1X20")
      (footprint "eagle-import:TSW1X20")
      (fields (field (name "PARTNUM") "?"))
      (libsource (lib "eagle-import") (part "TSW1X20"))
    )
    (comp (ref "J40")
      (value "BOARD00012")
      (footprint "eagle-import:TSW1X2")
      (libsource (lib "eagle-import") (part "BOARD00012"))
    )
    (comp (ref "J44")
      (value "MPT-08-01-01-L-RA-LC")
      (footprint "eagle-import:MPT-08-XX-X-RA-XX")
      (libsource (lib "eagle-import") (part "MPT-08-01-01-L-RA-LC"))
    )
    (comp (ref "J46")
      (value "BOARD00012")
      (footprint "eagle-import:TSW1X2")
      (libsource (lib "eagle-import") (part "BOARD00012"))
    )
    (comp (ref "J48")
      (value "BOARD00012")
      (footprint "eagle-import:TSW1X2")
      (libsource (lib "eagle-import") (part "BOARD00012"))
    )
    (comp (ref "J52")
      (value "BOARD00012")
      (footprint "eagle-import:TSW1X2")
      (libsource (lib "eagle-import") (part "BOARD00012"))
    )
    (comp (ref "J58")
      (value "BOARD00012")
      (footprint "eagle-import:TSW1X2")
      (libsource (lib "eagle-import") (part "BOARD00012"))
    )
    (comp (ref "J60")
      (value "BOARD00012")
      (footprint "eagle-import:TSW1X2")
      (libsource (lib "eagle-import") (part "BOARD00012"))
    )
    (comp (ref "J61")
      (value "TSW1X20")
      (footprint "eagle-import:TSW1X20")
      (fields (field (name "PARTNUM") "?"))
      (libsource (lib "eagle-import") (part "TSW1X20"))
    )
    (comp (ref "J64")
      (value "BOARD00012")
      (footprint "eagle-import:TSW1X2")
      (libsource (lib "eagle-import") (part "BOARD00012"))
    )
    (comp (ref "J65")
      (value "BOARD00012")
      (footprint "eagle-import:TSW1X2")
      (libsource (lib "eagle-import") (part "BOARD00012"))
    )
    (comp (ref "J66")
      (value "BOARD00012")
      (footprint "eagle-import:TSW1X2")
      (libsource (lib "eagle-import") (part "BOARD00012"))
    )
    (comp (ref "J67")
      (value "BOARD00012")
      (footprint "eagle-import:TSW1X2")
      (libsource (lib "eagle-import") (part "BOARD00012"))
    )
    (comp (ref "J68")
      (value "BOARD00012")
      (footprint "eagle-import:TSW1X2")
      (libsource (lib "eagle-import") (part "BOARD00012"))
    )
    (comp (ref "J69")
      (value "A1")
      (footprint "eagle-import:TSW1X1_VAL")
      (libsource (lib "eagle-import") (part "BOARD00003WVALUE"))
    )
    (comp (ref "J70")
      (value "BOARD00012")
      (footprint "eagle-import:TSW1X2")
      (libsource (lib "eagle-import") (part "BOARD00012"))
    )
    (comp (ref "J72")
      (value "A0")
      (footprint "eagle-import:TSW1X1_VAL")
      (libsource (lib "eagle-import") (part "BOARD00003WVALUE"))
    )
    (comp (ref "J73")
      (value "BOARD00012")
      (footprint "eagle-import:TSW1X2")
      (libsource (lib "eagle-import") (part "BOARD00012"))
    )
    (comp (ref "J75")
      (value "D2")
      (footprint "eagle-import:TSW1X1_VAL")
      (libsource (lib "eagle-import") (part "BOARD00003WVALUE"))
    )
    (comp (ref "J76")
      (value "BOARD00012")
      (footprint "eagle-import:TSW1X2")
      (libsource (lib "eagle-import") (part "BOARD00012"))
    )
    (comp (ref "J78")
      (value "D1")
      (footprint "eagle-import:TSW1X1_VAL")
      (libsource (lib "eagle-import") (part "BOARD00003WVALUE"))
    )
    (comp (ref "J79")
      (value "PCONN00012")
      (footprint "eagle-import:TSW3X4RA")
      (libsource (lib "eagle-import") (part "PCONN00012"))
    )
    (comp (ref "J80")
      (value "BOARD00012")
      (footprint "eagle-import:TSW1X2")
      (libsource (lib "eagle-import") (part "BOARD00012"))
    )
    (comp (ref "J82")
      (value "D0")
      (footprint "eagle-import:TSW1X1_VAL")
      (libsource (lib "eagle-import") (part "BOARD00003WVALUE"))
    )
    (comp (ref "J83")
      (value "BOARD00012")
      (footprint "eagle-import:TSW1X2")
      (libsource (lib "eagle-import") (part "BOARD00012"))
    )
    (comp (ref "J85")
      (value "SCL")
      (footprint "eagle-import:TSW1X1_VAL")
      (libsource (lib "eagle-import") (part "BOARD00003WVALUE"))
    )
    (comp (ref "J86")
      (value "BOARD00012")
      (footprint "eagle-import:TSW1X2")
      (libsource (lib "eagle-import") (part "BOARD00012"))
    )
    (comp (ref "J88")
      (value "SDA")
      (footprint "eagle-import:TSW1X1_VAL")
      (libsource (lib "eagle-import") (part "BOARD00003WVALUE"))
    )
    (comp (ref "J89")
      (value "BOARD00012")
      (footprint "eagle-import:TSW1X2")
      (libsource (lib "eagle-import") (part "BOARD00012"))
    )
    (comp (ref "J91")
      (value "GND")
      (footprint "eagle-import:TSW1X1_VAL")
      (libsource (lib "eagle-import") (part "BOARD00003WVALUE"))
    )
    (comp (ref "J92")
      (value "PCONN00012")
      (footprint "eagle-import:TSW3X4RA")
      (libsource (lib "eagle-import") (part "PCONN00012"))
    )
    (comp (ref "J93")
      (value "BOARD00012")
      (footprint "eagle-import:TSW1X2")
      (libsource (lib "eagle-import") (part "BOARD00012"))
    )
    (comp (ref "J95")
      (value "5.0V")
      (footprint "eagle-import:TSW1X1_VAL")
      (libsource (lib "eagle-import") (part "BOARD00003WVALUE"))
    )
    (comp (ref "J96")
      (value "BOARD00012")
      (footprint "eagle-import:TSW1X2")
      (libsource (lib "eagle-import") (part "BOARD00012"))
    )
    (comp (ref "J99")
      (value "GND")
      (footprint "eagle-import:TSW1X1_VAL")
      (fields (field (name "ACRONAME") "-") (field (name "PARTNUM") "-") (field (name "UNITCOST") "0.0"))
      (libsource (lib "eagle-import") (part "BOARD00003WVALUE"))
    )
    (comp (ref "J100")
      (value "GND")
      (footprint "eagle-import:TSW1X1_VAL")
      (fields (field (name "ACRONAME") "-") (field (name "PARTNUM") "-") (field (name "UNITCOST") "0.0"))
      (libsource (lib "eagle-import") (part "BOARD00003WVALUE"))
    )
    (comp (ref "M1")
      (value "MOUNT-HOLE3.2")
      (footprint "eagle-import:3,2")
      (libsource (lib "eagle-import") (part "MOUNT-HOLE3.2"))
    )
    (comp (ref "M2")
      (value "MOUNT-HOLE3.2")
      (footprint "eagle-import:3,2")
      (fields (field (name "ACRONAME") "-") (field (name "PARTNUM") "-") (field (name "SIZE") "3.2 mm"))
      (libsource (lib "eagle-import") (part "MOUNT-HOLE3.2"))
    )
    (comp (ref "M3")
      (value "MOUNT-HOLE3.2")
      (footprint "eagle-import:3,2")
      (libsource (lib "eagle-import") (part "MOUNT-HOLE3.2"))
    )
    (comp (ref "M4")
      (value "MOUNT-HOLE3.2")
      (footprint "eagle-import:3,2")
      (libsource (lib "eagle-import") (part "MOUNT-HOLE3.2"))
    )
    (comp (ref "M5")
      (value "MOUNT-HOLE3.2")
      (footprint "eagle-import:3,2")
      (fields (field (name "ACRONAME") "-") (field (name "PARTNUM") "-") (field (name "SIZE") "3.2 mm"))
      (libsource (lib "eagle-import") (part "MOUNT-HOLE3.2"))
    )
    (comp (ref "M6")
      (value "MOUNT-HOLE3.2")
      (footprint "eagle-import:3,2")
      (libsource (lib "eagle-import") (part "MOUNT-HOLE3.2"))
    )
    (comp (ref "M7")
      (value "BRAINSTEM_MOUNT")
      (footprint "eagle-import:BRAINSTEM_MOUNT")
      (libsource (lib "eagle-import") (part "BRAINSTEM_MOUNT"))
    )
    (comp (ref "R19")
      (value "PRESI00006")
      (footprint "eagle-import:R0603")
      (fields (field (name "PARTNUM") "ERJ-3EKF1001V"))
      (libsource (lib "eagle-import") (part "PRESI00006"))
    )
    (comp (ref "S2")
      (value "EVQ-PE104K")
      (footprint "eagle-import:SPST-NO")
      (libsource (lib "eagle-import") (part "EVQ-PE104K"))
    )
    (comp (ref "C1")
      (value "ECJ-1VC1H270J")
      (footprint "eagle-import:C0603")
      (libsource (lib "eagle-import") (part "ECJ-1VC1H270J"))
    )
    (comp (ref "C2")
      (value "T491B105K035AT")
      (footprint "eagle-import:T491")
      (libsource (lib "eagle-import") (part "T491B105K035AT"))
    )
    (comp (ref "C3")
      (value "T491B105K035AT")
      (footprint "eagle-import:T491")
      (libsource (lib "eagle-import") (part "T491B105K035AT"))
    )
    (comp (ref "C5")
      (value "PCAPI00005")
      (footprint "eagle-import:C0603")
      (libsource (lib "eagle-import") (part "PCAPI00005"))
    )
    (comp (ref "C8")
      (value "PCAPI00020")
      (footprint "eagle-import:PANASONIC_G")
      (fields (field (name "PARTNUM") "EEETG1V221UP"))
      (libsource (lib "eagle-import") (part "PCAPI00020"))
    )
    (comp (ref "C9")
      (value "CAP_POLARIZED")
      (footprint "eagle-import:PANASONIC_NHG_A")
      (fields (field (name "CAPACITANCE") "?"))
      (libsource (lib "eagle-import") (part "CAP_POLARIZED"))
    )
    (comp (ref "C12")
      (value "PCAPI00020")
      (footprint "eagle-import:PANASONIC_G")
      (fields (field (name "PARTNUM") "EEETG1V221UP"))
      (libsource (lib "eagle-import") (part "PCAPI00020"))
    )
    (comp (ref "C14")
      (value "CAP_POLARIZED")
      (footprint "eagle-import:PANASONIC_NHG_A")
      (fields (field (name "CAPACITANCE") "?"))
      (libsource (lib "eagle-import") (part "CAP_POLARIZED"))
    )
    (comp (ref "J1")
      (value "BOARD00003")
      (footprint "eagle-import:TSW1X1")
      (libsource (lib "eagle-import") (part "BOARD00003"))
    )
    (comp (ref "J4")
      (value "BOARD00003")
      (footprint "eagle-import:TSW1X1")
      (libsource (lib "eagle-import") (part "BOARD00003"))
    )
    (comp (ref "J5")
      (value "BOARD00003")
      (footprint "eagle-import:TSW1X1")
      (libsource (lib "eagle-import") (part "BOARD00003"))
    )
    (comp (ref "J6")
      (value "BOARD00003")
      (footprint "eagle-import:TSW1X1")
      (libsource (lib "eagle-import") (part "BOARD00003"))
    )
    (comp (ref "J7")
      (value "BOARD00003")
      (footprint "eagle-import:TSW1X1")
      (libsource (lib "eagle-import") (part "BOARD00003"))
    )
    (comp (ref "J8")
      (value "BOARD00003")
      (footprint "eagle-import:TSW1X1")
      (libsource (lib "eagle-import") (part "BOARD00003"))
    )
    (comp (ref "J10")
      (value "BOARD00003")
      (footprint "eagle-import:TSW1X1")
      (libsource (lib "eagle-import") (part "BOARD00003"))
    )
    (comp (ref "J11")
      (value "BOARD00003")
      (footprint "eagle-import:TSW1X1")
      (libsource (lib "eagle-import") (part "BOARD00003"))
    )
    (comp (ref "J13")
      (value "BOARD00003")
      (footprint "eagle-import:TSW1X1")
      (libsource (lib "eagle-import") (part "BOARD00003"))
    )
    (comp (ref "J31")
      (value "BOARD00012")
      (footprint "eagle-import:TSW1X2")
      (libsource (lib "eagle-import") (part "BOARD00012"))
    )
    (comp (ref "J32")
      (value "BOARD00012")
      (footprint "eagle-import:TSW1X2")
      (libsource (lib "eagle-import") (part "BOARD00012"))
    )
    (comp (ref "J33")
      (value "BOARD00012")
      (footprint "eagle-import:TSW1X2")
      (libsource (lib "eagle-import") (part "BOARD00012"))
    )
    (comp (ref "J35")
      (value "12.0V")
      (footprint "eagle-import:TSW1X1_VAL")
      (libsource (lib "eagle-import") (part "BOARD00003WVALUE"))
    )
    (comp (ref "L1")
      (value "7447709004")
      (footprint "eagle-import:7447709004")
      (libsource (lib "eagle-import") (part "7447709004"))
    )
    (comp (ref "Q1")
      (value "SI4322DY")
      (footprint "eagle-import:SO-08")
      (libsource (lib "eagle-import") (part "SI4322DY"))
    )
    (comp (ref "Q2")
      (value "SI4322DY")
      (footprint "eagle-import:SO-08")
      (libsource (lib "eagle-import") (part "SI4322DY"))
    )
    (comp (ref "Q3")
      (value "IXTA52P10P")
      (footprint "eagle-import:D2PACK")
      (libsource (lib "eagle-import") (part "IXTA52P10P"))
    )
    (comp (ref "R1")
      (value "PRESI00006")
      (footprint "eagle-import:R0603")
      (fields (field (name "PARTNUM") "ERJ-3EKF1001V"))
      (libsource (lib "eagle-import") (part "PRESI00006"))
    )
    (comp (ref "R2")
      (value "PRESI00006")
      (footprint "eagle-import:R0603")
      (fields (field (name "PARTNUM") "ERJ-3EKF1001V"))
      (libsource (lib "eagle-import") (part "PRESI00006"))
    )
    (comp (ref "R3")
      (value "ERJ-3EKF1004V")
      (footprint "eagle-import:R0603")
      (libsource (lib "eagle-import") (part "ERJ-3EKF1004V"))
    )
    (comp (ref "R4")
      (value "PRESI00006")
      (footprint "eagle-import:R0603")
      (fields (field (name "PARTNUM") "ERJ-3EKF1001V"))
      (libsource (lib "eagle-import") (part "PRESI00006"))
    )
    (comp (ref "R5")
      (value "PRESI00006")
      (footprint "eagle-import:R0603")
      (fields (field (name "PARTNUM") "ERJ-3EKF1001V"))
      (libsource (lib "eagle-import") (part "PRESI00006"))
    )
    (comp (ref "S1")
      (value "PMISC00005")
      (footprint "eagle-import:SPDTRA")
      (fields (field (name "PARTNUM") "1101M2S3AQE2"))
      (libsource (lib "eagle-import") (part "PMISC00005"))
    )
    (comp (ref "U1")
      (value "LM3150")
      (footprint "eagle-import:TSSOP14EXP")
      (libsource (lib "eagle-import") (part "LM3150"))
    )
    (comp (ref "C4")
      (value "T491D227K016ZT")
      (footprint "eagle-import:SMC_D")
      (fields (field (name "ACRONAME") "PCAPI00037"))
      (libsource (lib "eagle-import") (part "T491D227K016ZT"))
    )
    (comp (ref "C6")
      (value "T491D227K016ZT")
      (footprint "eagle-import:SMC_D")
      (fields (field (name "ACRONAME") "PCAPI00037"))
      (libsource (lib "eagle-import") (part "T491D227K016ZT"))
    )
    (comp (ref "C7")
      (value "T491D227K016ZT")
      (footprint "eagle-import:SMC_D")
      (fields (field (name "ACRONAME") "PCAPI00037"))
      (libsource (lib "eagle-import") (part "T491D227K016ZT"))
    )
    (comp (ref "C10")
      (value "T491D227K016ZT")
      (footprint "eagle-import:SMC_D")
      (fields (field (name "ACRONAME") "PCAPI00037"))
      (libsource (lib "eagle-import") (part "T491D227K016ZT"))
    )
    (comp (ref "C11")
      (value "T491D227K016ZT")
      (footprint "eagle-import:SMC_D")
      (fields (field (name "ACRONAME") "PCAPI00037"))
      (libsource (lib "eagle-import") (part "T491D227K016ZT"))
    )
    (comp (ref "C13")
      (value "T491D227K016ZT")
      (footprint "eagle-import:SMC_D")
      (fields (field (name "ACRONAME") "PCAPI00037"))
      (libsource (lib "eagle-import") (part "T491D227K016ZT"))
    )
    (comp (ref "J14")
      (value "3.3V")
      (footprint "eagle-import:TSW1X1_VAL")
      (fields (field (name "ACRONAME") "-") (field (name "PARTNUM") "-") (field (name "UNITCOST") "0.0"))
      (libsource (lib "eagle-import") (part "BOARD00003WVALUE"))
    )
    (comp (ref "J15")
      (value "BOARD00012")
      (footprint "eagle-import:TSW1X2")
      (libsource (lib "eagle-import") (part "BOARD00012"))
    )
    (comp (ref "J16")
      (value "5.0V")
      (footprint "eagle-import:TSW1X1_VAL")
      (libsource (lib "eagle-import") (part "BOARD00003WVALUE"))
    )
    (comp (ref "J17")
      (value "3.3V")
      (footprint "eagle-import:TSW1X1_VAL")
      (fields (field (name "ACRONAME") "-") (field (name "PARTNUM") "-") (field (name "UNITCOST") "0.0"))
      (libsource (lib "eagle-import") (part "BOARD00003WVALUE"))
    )
    (comp (ref "J18")
      (value "3.3V")
      (footprint "eagle-import:TSW1X1_VAL")
      (libsource (lib "eagle-import") (part "BOARD00003WVALUE"))
    )
    (comp (ref "J19")
      (value "3.3V")
      (footprint "eagle-import:TSW1X1_VAL")
      (fields (field (name "ACRONAME") "-") (field (name "PARTNUM") "-") (field (name "UNITCOST") "0.0"))
      (libsource (lib "eagle-import") (part "BOARD00003WVALUE"))
    )
    (comp (ref "J20")
      (value "BOARD00012")
      (footprint "eagle-import:TSW1X2")
      (libsource (lib "eagle-import") (part "BOARD00012"))
    )
    (comp (ref "J21")
      (value "9.0V")
      (footprint "eagle-import:TSW1X1_VAL")
      (libsource (lib "eagle-import") (part "BOARD00003WVALUE"))
    )
    (comp (ref "J22")
      (value "Router V+")
      (footprint "eagle-import:TSW1X1_VAL")
      (libsource (lib "eagle-import") (part "BOARD00003WVALUE"))
    )
    (comp (ref "J23")
      (value "BOARD00012")
      (footprint "eagle-import:TSW1X2")
      (libsource (lib "eagle-import") (part "BOARD00012"))
    )
    (comp (ref "J24")
      (value "Router V-")
      (footprint "eagle-import:TSW1X1_VAL")
      (libsource (lib "eagle-import") (part "BOARD00003WVALUE"))
    )
    (comp (ref "J98")
      (value "3.3V")
      (footprint "eagle-import:TSW1X1_VAL")
      (fields (field (name "ACRONAME") "-") (field (name "PARTNUM") "-") (field (name "UNITCOST") "0.0"))
      (libsource (lib "eagle-import") (part "BOARD00003WVALUE"))
    )
    (comp (ref "R6")
      (value "on")
      (footprint "eagle-import:R0603")
      (fields
        (field (name "PARTNUM") "ERJ-3GEYJ332V")
        (field (name "ACRONAME") "PRESI00002")
        (field (name "PARTNUM_1") "ERJ-3GEYJ332V")
      )
      (libsource (lib "eagle-import") (part "PRESI00002"))
    )
    (comp (ref "R7")
      (value "PRESI00007")
      (footprint "eagle-import:R0603")
      (fields
        (field (name "PARTNUM") "ERJ-3GEYJ222V")
        (field (name "ACRONAME") "PRESI00007")
        (field (name "PARTNUM_1") "ERJ-3GEYJ222V")
      )
      (libsource (lib "eagle-import") (part "PRESI00007"))
    )
    (comp (ref "R8")
      (value "PRESI00019")
      (footprint "eagle-import:R0603")
      (fields
        (field (name "PARTNUM") "ERJ-3EKF2431V")
        (field (name "ACRONAME") "PRESI00019")
        (field (name "PARTNUM_1") "ERJ-3EKF2431V")
      )
      (libsource (lib "eagle-import") (part "PRESI00019"))
    )
    (comp (ref "R9")
      (value "on")
      (footprint "eagle-import:R0402")
      (fields
        (field (name "PARTNUM") "ERJ-3EKF6491V")
        (field (name "ACRONAME") "PRESI00056")
        (field (name "PARTNUM_1") "ERJ-3EKF6491V")
      )
      (libsource (lib "eagle-import") (part "PRESI00056"))
    )
    (comp (ref "R10")
      (value "PRESI00039")
      (footprint "eagle-import:R0603")
      (fields
        (field (name "PARTNUM") "ERJ-3EKF6980V")
        (field (name "ACRONAME") "PRESI00039")
        (field (name "PARTNUM_1") "ERJ-3EKF6980V")
      )
      (libsource (lib "eagle-import") (part "PRESI00039"))
    )
    (comp (ref "R11")
      (value "on")
      (footprint "eagle-import:R0603")
      (fields (field (name "RESISTANCE") "4.22k"))
      (libsource (lib "eagle-import") (part "RESISTOR"))
    )
    (comp (ref "U2")
      (value "LM1084IS-ADJ")
      (footprint "eagle-import:TO263-3")
      (fields (field (name "PARTNUM") "LM1084IS-ADJ/NOPB"))
      (libsource (lib "eagle-import") (part "LM1084IS-ADJ"))
    )
    (comp (ref "U3")
      (value "LM1084IS-ADJ")
      (footprint "eagle-import:TO263-3")
      (fields (field (name "PARTNUM") "LM1084IS-ADJ/NOPB"))
      (libsource (lib "eagle-import") (part "LM1084IS-ADJ"))
    )
    (comp (ref "U4")
      (value "LM1084IS-ADJ")
      (footprint "eagle-import:TO263-3")
      (fields (field (name "PARTNUM") "LM1084IS-ADJ/NOPB"))
      (libsource (lib "eagle-import") (part "LM1084IS-ADJ"))
    )
    (comp (ref "C24")
      (value "T491A106K010AT")
      (footprint "eagle-import:SMC_A")
      (fields (field (name "PARTNUM") "T491A106M016AT"))
      (libsource (lib "eagle-import") (part "T491A106K010AT"))
    )
    (comp (ref "J71")
      (value "BOARD00012")
      (footprint "eagle-import:TSW1X2")
      (libsource (lib "eagle-import") (part "BOARD00012"))
    )
    (comp (ref "J74")
      (value "BOARD00012")
      (footprint "eagle-import:TSW1X2")
      (libsource (lib "eagle-import") (part "BOARD00012"))
    )
    (comp (ref "J77")
      (value "BOARD00012")
      (footprint "eagle-import:TSW1X2")
      (libsource (lib "eagle-import") (part "BOARD00012"))
    )
    (comp (ref "J81")
      (value "BOARD00012")
      (footprint "eagle-import:TSW1X2")
      (libsource (lib "eagle-import") (part "BOARD00012"))
    )
    (comp (ref "J84")
      (value "BOARD00012")
      (footprint "eagle-import:TSW1X2")
      (libsource (lib "eagle-import") (part "BOARD00012"))
    )
    (comp (ref "J87")
      (value "BOARD00012")
      (footprint "eagle-import:TSW1X2")
      (libsource (lib "eagle-import") (part "BOARD00012"))
    )
    (comp (ref "J90")
      (value "BOARD00012")
      (footprint "eagle-import:TSW1X2")
      (libsource (lib "eagle-import") (part "BOARD00012"))
    )
    (comp (ref "J94")
      (value "BOARD00012")
      (footprint "eagle-import:TSW1X2")
      (libsource (lib "eagle-import") (part "BOARD00012"))
    )
    (comp (ref "L2")
      (value "PMISC00013")
      (footprint "eagle-import:L0402")
      (fields (field (name "PARTNUM") "LI0402E300R-10"))
      (libsource (lib "eagle-import") (part "PMISC00013"))
    )
    (comp (ref "U9")
      (value "ADS7828E")
      (footprint "eagle-import:TSSOP16")
      (fields (field (name "PARTNUM") "ADS7828E/250"))
      (libsource (lib "eagle-import") (part "ADS7828E"))
    )
  )
  (nets
    (net (code "1") (name "3V3") (class "Default")
      (node (ref "C23") (pin "2") (pinfunction "2_2") (pintype "passive"))
      (node (ref "C24") (pin "+") (pinfunction "+_+") (pintype "passive"))
      (node (ref "C25") (pin "1") (pinfunction "1_1") (pintype "passive"))
      (node (ref "C26") (pin "2") (pinfunction "2_2") (pintype "passive"))
      (node (ref "D10") (pin "A") (pinfunction "A_A") (pintype "passive"))
      (node (ref "D11") (pin "A") (pinfunction "A_A") (pintype "passive"))
      (node (ref "D4") (pin "A") (pinfunction "A_A") (pintype "passive"))
      (node (ref "D5") (pin "A") (pinfunction "A_A") (pintype "passive"))
      (node (ref "D6") (pin "A") (pinfunction "A_A") (pintype "passive"))
      (node (ref "D7") (pin "A") (pinfunction "A_A") (pintype "passive"))
      (node (ref "D8") (pin "A") (pinfunction "A_A") (pintype "passive"))
      (node (ref "D9") (pin "A") (pinfunction "A_A") (pintype "passive"))
      (node (ref "J14") (pin "P$1") (pinfunction "P$3_P$1") (pintype "bidirectional"))
      (node (ref "J15") (pin "P$1") (pinfunction "P$1_P$1") (pintype "bidirectional"))
      (node (ref "J17") (pin "P$1") (pinfunction "P$3_P$1") (pintype "bidirectional"))
      (node (ref "J18") (pin "P$1") (pinfunction "P$3_P$1") (pintype "bidirectional"))
      (node (ref "J19") (pin "P$1") (pinfunction "P$3_P$1") (pintype "bidirectional"))
      (node (ref "J29") (pin "P$2") (pinfunction "P$2_P$2") (pintype "bidirectional"))
      (node (ref "J34") (pin "3.3V") (pinfunction "P$19_3.3V") (pintype "bidirectional"))
      (node (ref "J34") (pin "RTCV") (pinfunction "P$18_RTCV") (pintype "bidirectional"))
      (node (ref "J38") (pin "P$2") (pinfunction "P$2_P$2") (pintype "bidirectional"))
      (node (ref "J46") (pin "P$1") (pinfunction "P$1_P$1") (pintype "bidirectional"))
      (node (ref "J50") (pin "P$2") (pinfunction "P$2_P$2") (pintype "bidirectional"))
      (node (ref "J53") (pin "P$2") (pinfunction "P$2_P$2") (pintype "bidirectional"))
      (node (ref "J61") (pin "P$18") (pinfunction "P$18_P$18") (pintype "bidirectional"))
      (node (ref "J61") (pin "P$19") (pinfunction "P$19_P$19") (pintype "bidirectional"))
      (node (ref "J98") (pin "P$1") (pinfunction "P$3_P$1") (pintype "bidirectional"))
      (node (ref "R14") (pin "2") (pinfunction "2_2") (pintype "passive"))
      (node (ref "R19") (pin "2") (pinfunction "2_2") (pintype "passive"))
      (node (ref "R21") (pin "2") (pinfunction "2_2") (pintype "passive"))
      (node (ref "R22") (pin "2") (pinfunction "2_2") (pintype "passive"))
      (node (ref "S3") (pin "3") (pinfunction "2_3") (pintype "bidirectional"))
      (node (ref "U10") (pin "16") (pinfunction "VCC_16") (pintype "power_in"))
      (node (ref "U13") (pin "5") (pinfunction "VCC_5") (pintype "power_in"))
      (node (ref "U8") (pin "5") (pinfunction "VCC_5") (pintype "power_in"))
      (node (ref "U9") (pin "16") (pinfunction "VDD_16") (pintype "bidirectional"))
    )
    (net (code "2") (name "5V0") (class "Default")
      (node (ref "C6") (pin "+") (pinfunction "+_+") (pintype "passive"))
      (node (ref "J16") (pin "P$1") (pinfunction "P$3_P$1") (pintype "bidirectional"))
      (node (ref "J20") (pin "P$1") (pinfunction "P$1_P$1") (pintype "bidirectional"))
      (node (ref "J48") (pin "P$1") (pinfunction "P$1_P$1") (pintype "bidirectional"))
      (node (ref "J79") (pin "P$5") (pinfunction "P$8_P$5") (pintype "bidirectional"))
      (node (ref "J79") (pin "P$6") (pinfunction "P$7_P$6") (pintype "bidirectional"))
      (node (ref "J79") (pin "P$7") (pinfunction "P$6_P$7") (pintype "bidirectional"))
      (node (ref "J79") (pin "P$8") (pinfunction "P$5_P$8") (pintype "bidirectional"))
      (node (ref "J92") (pin "P$5") (pinfunction "P$8_P$5") (pintype "bidirectional"))
      (node (ref "J92") (pin "P$6") (pinfunction "P$7_P$6") (pintype "bidirectional"))
      (node (ref "J92") (pin "P$7") (pinfunction "P$6_P$7") (pintype "bidirectional"))
      (node (ref "J92") (pin "P$8") (pinfunction "P$5_P$8") (pintype "bidirectional"))
      (node (ref "J95") (pin "P$1") (pinfunction "P$3_P$1") (pintype "bidirectional"))
      (node (ref "L2") (pin "2") (pinfunction "2_2") (pintype "passive"))
      (node (ref "U2") (pin "3") (pinfunction "INPUT_3") (pintype "bidirectional"))
    )
    (net (code "3") (name "6V0") (class "Default")
      (node (ref "J52") (pin "P$1") (pinfunction "P$1_P$1") (pintype "bidirectional"))
    )
    (net (code "4") (name "9.0V") (class "Default")
      (node (ref "C10") (pin "+") (pinfunction "+_+") (pintype "passive"))
      (node (ref "J21") (pin "P$1") (pinfunction "P$3_P$1") (pintype "bidirectional"))
      (node (ref "J22") (pin "P$1") (pinfunction "P$3_P$1") (pintype "bidirectional"))
      (node (ref "J23") (pin "P$1") (pinfunction "P$1_P$1") (pintype "bidirectional"))
      (node (ref "U3") (pin "3") (pinfunction "INPUT_3") (pintype "bidirectional"))
    )
    (net (code "5") (name "12.0V") (class "Default")
      (node (ref "C13") (pin "+") (pinfunction "+_+") (pintype "passive"))
      (node (ref "J31") (pin "P$1") (pinfunction "P$1_P$1") (pintype "bidirectional"))
      (node (ref "J32") (pin "P$1") (pinfunction "P$1_P$1") (pintype "bidirectional"))
      (node (ref "J33") (pin "P$1") (pinfunction "P$1_P$1") (pintype "bidirectional"))
      (node (ref "J35") (pin "P$1") (pinfunction "P$3_P$1") (pintype "bidirectional"))
      (node (ref "J44") (pin "5@0") (pinfunction "5_5@0") (pintype "bidirectional"))
      (node (ref "J44") (pin "5@1") (pinfunction "5_5@1") (pintype "bidirectional"))
      (node (ref "J44") (pin "5@2") (pinfunction "5_5@2") (pintype "bidirectional"))
      (node (ref "J44") (pin "5@3") (pinfunction "5_5@3") (pintype "bidirectional"))
      (node (ref "J44") (pin "5@4") (pinfunction "5_5@4") (pintype "bidirectional"))
      (node (ref "J44") (pin "5@5") (pinfunction "5_5@5") (pintype "bidirectional"))
      (node (ref "U4") (pin "3") (pinfunction "INPUT_3") (pintype "bidirectional"))
    )
    (net (code "6") (name "A2D0") (class "Default")
      (node (ref "J34") (pin "A2D0") (pinfunction "P$8_A2D0") (pintype "bidirectional"))
      (node (ref "J37") (pin "P$8") (pinfunction "P$8_P$8") (pintype "bidirectional"))
      (node (ref "J57") (pin "P$1") (pinfunction "P$1_P$1") (pintype "bidirectional"))
    )
    (net (code "7") (name "A2D1") (class "Default")
      (node (ref "J34") (pin "A2D1") (pinfunction "P$9_A2D1") (pintype "bidirectional"))
      (node (ref "J37") (pin "P$9") (pinfunction "P$9_P$9") (pintype "bidirectional"))
      (node (ref "J56") (pin "P$1") (pinfunction "P$1_P$1") (pintype "bidirectional"))
    )
    (net (code "8") (name "A2D2") (class "Default")
      (node (ref "J34") (pin "A2D2") (pinfunction "P$10_A2D2") (pintype "bidirectional"))
      (node (ref "J37") (pin "P$10") (pinfunction "P$10_P$10") (pintype "bidirectional"))
      (node (ref "J55") (pin "P$1") (pinfunction "P$1_P$1") (pintype "bidirectional"))
    )
    (net (code "9") (name "BATTERY_MOTOR+_IN") (class "Default")
      (node (ref "J44") (pin "1@0") (pinfunction "1_1@0") (pintype "bidirectional"))
      (node (ref "J44") (pin "1@1") (pinfunction "1_1@1") (pintype "bidirectional"))
      (node (ref "J44") (pin "1@2") (pinfunction "1_1@2") (pintype "bidirectional"))
      (node (ref "J44") (pin "1@3") (pinfunction "1_1@3") (pintype "bidirectional"))
      (node (ref "J44") (pin "1@4") (pinfunction "1_1@4") (pintype "bidirectional"))
      (node (ref "J44") (pin "1@5") (pinfunction "1_1@5") (pintype "bidirectional"))
      (node (ref "Q4") (pin "D") (pinfunction "D_D") (pintype "bidirectional"))
      (node (ref "Q5") (pin "D") (pinfunction "D_D") (pintype "bidirectional"))
      (node (ref "Q6") (pin "D") (pinfunction "D_D") (pintype "bidirectional"))
      (node (ref "U11") (pin "2") (pinfunction "VDD_2") (pintype "bidirectional"))
      (node (ref "U12") (pin "4") (pinfunction "COL_4") (pintype "bidirectional"))
    )
    (net (code "10") (name "BATTERY_MOTOR+_OUT") (class "Default")
      (node (ref "J43") (pin "P$1") (pinfunction "P$1_P$1") (pintype "bidirectional"))
      (node (ref "J44") (pin "3@0") (pinfunction "3_3@0") (pintype "bidirectional"))
      (node (ref "J44") (pin "3@1") (pinfunction "3_3@1") (pintype "bidirectional"))
      (node (ref "J44") (pin "3@2") (pinfunction "3_3@2") (pintype "bidirectional"))
      (node (ref "J44") (pin "3@3") (pinfunction "3_3@3") (pintype "bidirectional"))
      (node (ref "J44") (pin "3@4") (pinfunction "3_3@4") (pintype "bidirectional"))
      (node (ref "J44") (pin "3@5") (pinfunction "3_3@5") (pintype "bidirectional"))
      (node (ref "R13") (pin "2") (pinfunction "2_2") (pintype "passive"))
      (node (ref "R18") (pin "2") (pinfunction "2_2") (pintype "passive"))
      (node (ref "U8") (pin "3") (pinfunction "VIN+_3") (pintype "bidirectional"))
    )
    (net (code "11") (name "BATTERY_MOTOR+_OUT_PRE") (class "Default")
      (node (ref "J42") (pin "P$1") (pinfunction "P$1_P$1") (pintype "bidirectional"))
      (node (ref "Q4") (pin "S") (pinfunction "S_S") (pintype "bidirectional"))
      (node (ref "Q5") (pin "S") (pinfunction "S_S") (pintype "bidirectional"))
      (node (ref "Q6") (pin "S") (pinfunction "S_S") (pintype "bidirectional"))
      (node (ref "R13") (pin "1") (pinfunction "1_1") (pintype "passive"))
      (node (ref "R16") (pin "2") (pinfunction "2_2") (pintype "passive"))
      (node (ref "U8") (pin "4") (pinfunction "VIN-_4") (pintype "bidirectional"))
    )
    (net (code "12") (name "DIO0") (class "Default")
      (node (ref "J34") (pin "DIO0") (pinfunction "P$1_DIO0") (pintype "bidirectional"))
      (node (ref "J61") (pin "P$1") (pinfunction "P$1_P$1") (pintype "bidirectional"))
    )
    (net (code "13") (name "DIO1") (class "Default")
      (node (ref "J34") (pin "DIO1") (pinfunction "P$2_DIO1") (pintype "bidirectional"))
      (node (ref "J61") (pin "P$2") (pinfunction "P$2_P$2") (pintype "bidirectional"))
    )
    (net (code "14") (name "DIO2") (class "Default")
      (node (ref "J34") (pin "DIO2") (pinfunction "P$3_DIO2") (pintype "bidirectional"))
      (node (ref "J61") (pin "P$3") (pinfunction "P$3_P$3") (pintype "bidirectional"))
    )
    (net (code "15") (name "DIO3") (class "Default")
      (node (ref "J34") (pin "DIO3") (pinfunction "P$4_DIO3") (pintype "bidirectional"))
      (node (ref "J61") (pin "P$4") (pinfunction "P$4_P$4") (pintype "bidirectional"))
    )
    (net (code "16") (name "DIO4") (class "Default")
      (node (ref "J34") (pin "DIO4") (pinfunction "P$5_DIO4") (pintype "bidirectional"))
      (node (ref "J61") (pin "P$5") (pinfunction "P$5_P$5") (pintype "bidirectional"))
    )
    (net (code "17") (name "DIO5") (class "Default")
      (node (ref "J34") (pin "DIO5") (pinfunction "P$6_DIO5") (pintype "bidirectional"))
      (node (ref "J61") (pin "P$6") (pinfunction "P$6_P$6") (pintype "bidirectional"))
    )
    (net (code "18") (name "DIO6") (class "Default")
      (node (ref "J34") (pin "DIO6") (pinfunction "P$7_DIO6") (pintype "bidirectional"))
      (node (ref "J61") (pin "P$7") (pinfunction "P$7_P$7") (pintype "bidirectional"))
    )
    (net (code "19") (name "DIO7") (class "Default")
      (node (ref "J34") (pin "DIO7") (pinfunction "P$8_DIO7") (pintype "bidirectional"))
      (node (ref "J61") (pin "P$8") (pinfunction "P$8_P$8") (pintype "bidirectional"))
    )
    (net (code "20") (name "DIO8") (class "Default")
      (node (ref "J34") (pin "DIO8") (pinfunction "P$9_DIO8") (pintype "bidirectional"))
      (node (ref "J61") (pin "P$9") (pinfunction "P$9_P$9") (pintype "bidirectional"))
    )
    (net (code "21") (name "DIO9") (class "Default")
      (node (ref "J34") (pin "DIO9") (pinfunction "P$10_DIO9") (pintype "bidirectional"))
      (node (ref "J61") (pin "P$10") (pinfunction "P$10_P$10") (pintype "bidirectional"))
    )
    (net (code "22") (name "DIO10") (class "Default")
      (node (ref "J34") (pin "DIO10/SDA1") (pinfunction "P$11_DIO10/SDA1") (pintype "bidirectional"))
      (node (ref "J61") (pin "P$11") (pinfunction "P$11_P$11") (pintype "bidirectional"))
    )
    (net (code "23") (name "DIO11") (class "Default")
      (node (ref "J34") (pin "DIO11/SCL1") (pinfunction "P$12_DIO11/SCL1") (pintype "bidirectional"))
      (node (ref "J61") (pin "P$12") (pinfunction "P$12_P$12") (pintype "bidirectional"))
    )
    (net (code "24") (name "ESC_EN") (class "Default")
      (node (ref "J86") (pin "P$2") (pinfunction "P$2_P$2") (pintype "bidirectional"))
    )
    (net (code "25") (name "GND") (class "Default")
      (node (ref "C1") (pin "2") (pinfunction "2_2") (pintype "passive"))
      (node (ref "C10") (pin "-") (pinfunction "-_-") (pintype "passive"))
      (node (ref "C11") (pin "-") (pinfunction "-_-") (pintype "passive"))
      (node (ref "C12") (pin "-") (pinfunction "-_-") (pintype "passive"))
      (node (ref "C13") (pin "-") (pinfunction "-_-") (pintype "passive"))
      (node (ref "C14") (pin "-") (pinfunction "-_-") (pintype "passive"))
      (node (ref "C16") (pin "2") (pinfunction "2_2") (pintype "passive"))
      (node (ref "C17") (pin "2") (pinfunction "2_2") (pintype "passive"))
      (node (ref "C18") (pin "2") (pinfunction "2_2") (pintype "passive"))
      (node (ref "C19") (pin "2") (pinfunction "2_2") (pintype "passive"))
      (node (ref "C2") (pin "-") (pinfunction "-_-") (pintype "passive"))
      (node (ref "C20") (pin "2") (pinfunction "2_2") (pintype "passive"))
      (node (ref "C21") (pin "2") (pinfunction "2_2") (pintype "passive"))
      (node (ref "C22") (pin "-") (pinfunction "-_-") (pintype "passive"))
      (node (ref "C23") (pin "1") (pinfunction "1_1") (pintype "passive"))
      (node (ref "C24") (pin "-") (pinfunction "-_-") (pintype "passive"))
      (node (ref "C25") (pin "2") (pinfunction "2_2") (pintype "passive"))
      (node (ref "C26") (pin "1") (pinfunction "1_1") (pintype "passive"))
      (node (ref "C3") (pin "-") (pinfunction "-_-") (pintype "passive"))
      (node (ref "C4") (pin "-") (pinfunction "-_-") (pintype "passive"))
      (node (ref "C6") (pin "-") (pinfunction "-_-") (pintype "passive"))
      (node (ref "C7") (pin "-") (pinfunction "-_-") (pintype "passive"))
      (node (ref "C8") (pin "-") (pinfunction "-_-") (pintype "passive"))
      (node (ref "C9") (pin "-") (pinfunction "-_-") (pintype "passive"))
      (node (ref "J1") (pin "P$1") (pinfunction "P$3_P$1") (pintype "bidirectional"))
      (node (ref "J100") (pin "P$1") (pinfunction "P$3_P$1") (pintype "bidirectional"))
      (node (ref "J12") (pin "P$1") (pinfunction "P$3_P$1") (pintype "bidirectional"))
      (node (ref "J2") (pin "P$1") (pinfunction "P$3_P$1") (pintype "bidirectional"))
      (node (ref "J24") (pin "P$1") (pinfunction "P$3_P$1") (pintype "bidirectional"))
      (node (ref "J28") (pin "P$2") (pinfunction "P$2_P$2") (pintype "bidirectional"))
      (node (ref "J3") (pin "P$1") (pinfunction "P$3_P$1") (pintype "bidirectional"))
      (node (ref "J34") (pin "GND") (pinfunction "P$20_GND") (pintype "bidirectional"))
      (node (ref "J40") (pin "P$1") (pinfunction "P$1_P$1") (pintype "bidirectional"))
      (node (ref "J41") (pin "P$2") (pinfunction "P$2_P$2") (pintype "bidirectional"))
      (node (ref "J44") (pin "6@0") (pinfunction "6_6@0") (pintype "bidirectional"))
      (node (ref "J44") (pin "6@1") (pinfunction "6_6@1") (pintype "bidirectional"))
      (node (ref "J44") (pin "6@2") (pinfunction "6_6@2") (pintype "bidirectional"))
      (node (ref "J44") (pin "6@3") (pinfunction "6_6@3") (pintype "bidirectional"))
      (node (ref "J44") (pin "6@4") (pinfunction "6_6@4") (pintype "bidirectional"))
      (node (ref "J44") (pin "6@5") (pinfunction "6_6@5") (pintype "bidirectional"))
      (node (ref "J44") (pin "8@0") (pinfunction "1_8@0") (pintype "bidirectional"))
      (node (ref "J44") (pin "8@1") (pinfunction "1_8@1") (pintype "bidirectional"))
      (node (ref "J44") (pin "8@2") (pinfunction "1_8@2") (pintype "bidirectional"))
      (node (ref "J44") (pin "8@3") (pinfunction "1_8@3") (pintype "bidirectional"))
      (node (ref "J44") (pin "8@4") (pinfunction "1_8@4") (pintype "bidirectional"))
      (node (ref "J44") (pin "8@5") (pinfunction "8_8@5") (pintype "bidirectional"))
      (node (ref "J51") (pin "P$1") (pinfunction "P$3_P$1") (pintype "bidirectional"))
      (node (ref "J61") (pin "P$20") (pinfunction "P$20_P$20") (pintype "bidirectional"))
      (node (ref "J79") (pin "P$1") (pinfunction "P$1_P$1") (pintype "bidirectional"))
      (node (ref "J79") (pin "P$2") (pinfunction "P$2_P$2") (pintype "bidirectional"))
      (node (ref "J79") (pin "P$3") (pinfunction "P$3_P$3") (pintype "bidirectional"))
      (node (ref "J79") (pin "P$4") (pinfunction "P$4_P$4") (pintype "bidirectional"))
      (node (ref "J9") (pin "P$1") (pinfunction "P$3_P$1") (pintype "bidirectional"))
      (node (ref "J91") (pin "P$1") (pinfunction "P$3_P$1") (pintype "bidirectional"))
      (node (ref "J92") (pin "P$1") (pinfunction "P$1_P$1") (pintype "bidirectional"))
      (node (ref "J92") (pin "P$2") (pinfunction "P$2_P$2") (pintype "bidirectional"))
      (node (ref "J92") (pin "P$3") (pinfunction "P$3_P$3") (pintype "bidirectional"))
      (node (ref "J92") (pin "P$4") (pinfunction "P$4_P$4") (pintype "bidirectional"))
      (node (ref "J99") (pin "P$1") (pinfunction "P$3_P$1") (pintype "bidirectional"))
      (node (ref "R11") (pin "1") (pinfunction "1_1") (pintype "passive"))
      (node (ref "R12") (pin "2") (pinfunction "2_2") (pintype "passive"))
      (node (ref "R15") (pin "1") (pinfunction "1_1") (pintype "passive"))
      (node (ref "R2") (pin "2") (pinfunction "2_2") (pintype "passive"))
      (node (ref "R3") (pin "2") (pinfunction "2_2") (pintype "passive"))
      (node (ref "R6") (pin "1") (pinfunction "1_1") (pintype "passive"))
      (node (ref "R9") (pin "1") (pinfunction "1_1") (pintype "passive"))
      (node (ref "S1") (pin "1") (pinfunction "3_1") (pintype "bidirectional"))
      (node (ref "S2") (pin "P$1") (pinfunction "P_P$1") (pintype "passive"))
      (node (ref "S3") (pin "1") (pinfunction "3_1") (pintype "bidirectional"))
      (node (ref "U10") (pin "1") (pinfunction "AD0_1") (pintype "bidirectional"))
      (node (ref "U10") (pin "2") (pinfunction "AD1_2") (pintype "bidirectional"))
      (node (ref "U10") (pin "3") (pinfunction "AD2_3") (pintype "bidirectional"))
      (node (ref "U10") (pin "8") (pinfunction "GND_8") (pintype "power_in"))
      (node (ref "U12") (pin "2") (pinfunction "CATH_2") (pintype "bidirectional"))
      (node (ref "U13") (pin "3") (pinfunction "GND_3") (pintype "power_in"))
      (node (ref "U5") (pin "10") (pinfunction "RES_10") (pintype "bidirectional"))
      (node (ref "U5") (pin "11") (pinfunction "RES_11") (pintype "bidirectional"))
      (node (ref "U5") (pin "12") (pinfunction "RES_12") (pintype "bidirectional"))
      (node (ref "U5") (pin "13") (pinfunction "GND_13") (pintype "bidirectional"))
      (node (ref "U5") (pin "15") (pinfunction "RES_15") (pintype "bidirectional"))
      (node (ref "U5") (pin "8") (pinfunction "RES_8") (pintype "bidirectional"))
      (node (ref "U5") (pin "9") (pinfunction "RES_9") (pintype "bidirectional"))
      (node (ref "U6") (pin "3") (pinfunction "COM_3") (pintype "bidirectional"))
      (node (ref "U6") (pin "5") (pinfunction "COM_5") (pintype "bidirectional"))
      (node (ref "U6") (pin "6") (pinfunction "COM_6") (pintype "bidirectional"))
      (node (ref "U6") (pin "7") (pinfunction "COM_7") (pintype "bidirectional"))
      (node (ref "U7") (pin "GND") (pinfunction "GND_GND") (pintype "bidirectional"))
      (node (ref "U8") (pin "2") (pinfunction "GND_2") (pintype "power_in"))
      (node (ref "U9") (pin "11") (pinfunction "COM_11") (pintype "bidirectional"))
      (node (ref "U9") (pin "12") (pinfunction "AD0_12") (pintype "bidirectional"))
      (node (ref "U9") (pin "13") (pinfunction "AD1_13") (pintype "bidirectional"))
      (node (ref "U9") (pin "9") (pinfunction "GND_9") (pintype "bidirectional"))
    )
    (net (code "26") (name "GND3") (class "Default")
      (node (ref "D1") (pin "C") (pinfunction "C_C") (pintype "passive"))
      (node (ref "D2") (pin "C") (pinfunction "A_C") (pintype "passive"))
      (node (ref "J44") (pin "2@0") (pinfunction "2_2@0") (pintype "bidirectional"))
      (node (ref "J44") (pin "2@1") (pinfunction "2_2@1") (pintype "bidirectional"))
      (node (ref "J44") (pin "2@2") (pinfunction "2_2@2") (pintype "bidirectional"))
      (node (ref "J44") (pin "2@3") (pinfunction "2_2@3") (pintype "bidirectional"))
      (node (ref "J44") (pin "2@4") (pinfunction "2_2@4") (pintype "bidirectional"))
      (node (ref "J44") (pin "2@5") (pinfunction "2_2@5") (pintype "bidirectional"))
      (node (ref "J44") (pin "4@0") (pinfunction "4_4@0") (pintype "bidirectional"))
      (node (ref "J44") (pin "4@1") (pinfunction "4_4@1") (pintype "bidirectional"))
      (node (ref "J44") (pin "4@2") (pinfunction "4_4@2") (pintype "bidirectional"))
      (node (ref "J44") (pin "4@3") (pinfunction "4_4@3") (pintype "bidirectional"))
      (node (ref "J44") (pin "4@4") (pinfunction "4_4@4") (pintype "bidirectional"))
      (node (ref "J44") (pin "4@5") (pinfunction "4_4@5") (pintype "bidirectional"))
      (node (ref "J63") (pin "P$1") (pinfunction "P$3_P$1") (pintype "bidirectional"))
      (node (ref "R17") (pin "1") (pinfunction "1_1") (pintype "passive"))
      (node (ref "R20") (pin "1") (pinfunction "1_1") (pintype "passive"))
      (node (ref "U11") (pin "4") (pinfunction "GND_4") (pintype "bidirectional"))
    )
    (net (code "27") (name "GP2_D1") (class "Default")
      (node (ref "J67") (pin "P$1") (pinfunction "P$1_P$1") (pintype "bidirectional"))
      (node (ref "J78") (pin "P$1") (pinfunction "P$3_P$1") (pintype "bidirectional"))
    )
    (net (code "28") (name "GP2_D2") (class "Default")
      (node (ref "J66") (pin "P$1") (pinfunction "P$1_P$1") (pintype "bidirectional"))
      (node (ref "J75") (pin "P$1") (pinfunction "P$3_P$1") (pintype "bidirectional"))
    )
    (net (code "29") (name "I2C_CH0") (class "Default")
      (node (ref "J71") (pin "P$2") (pinfunction "P$2_P$2") (pintype "bidirectional"))
      (node (ref "J79") (pin "P$9") (pinfunction "P$9_P$9") (pintype "bidirectional"))
    )
    (net (code "30") (name "I2C_CH1") (class "Default")
      (node (ref "J74") (pin "P$2") (pinfunction "P$2_P$2") (pintype "bidirectional"))
      (node (ref "J79") (pin "P$10") (pinfunction "P$10_P$10") (pintype "bidirectional"))
    )
    (net (code "31") (name "I2C_CH2") (class "Default")
      (node (ref "J77") (pin "P$2") (pinfunction "P$2_P$2") (pintype "bidirectional"))
      (node (ref "J79") (pin "P$11") (pinfunction "P$11_P$11") (pintype "bidirectional"))
    )
    (net (code "32") (name "I2C_CH3") (class "Default")
      (node (ref "J79") (pin "P$12") (pinfunction "P$12_P$12") (pintype "bidirectional"))
      (node (ref "J81") (pin "P$2") (pinfunction "P$2_P$2") (pintype "bidirectional"))
    )
    (net (code "33") (name "I2C_CH4") (class "Default")
      (node (ref "J84") (pin "P$2") (pinfunction "P$2_P$2") (pintype "bidirectional"))
      (node (ref "J92") (pin "P$9") (pinfunction "P$9_P$9") (pintype "bidirectional"))
    )
    (net (code "34") (name "I2C_CH5") (class "Default")
      (node (ref "J87") (pin "P$2") (pinfunction "P$2_P$2") (pintype "bidirectional"))
      (node (ref "J92") (pin "P$10") (pinfunction "P$10_P$10") (pintype "bidirectional"))
    )
    (net (code "35") (name "I2C_CH6") (class "Default")
      (node (ref "J90") (pin "P$2") (pinfunction "P$2_P$2") (pintype "bidirectional"))
      (node (ref "J92") (pin "P$11") (pinfunction "P$11_P$11") (pintype "bidirectional"))
    )
    (net (code "36") (name "I2C_CH7") (class "Default")
      (node (ref "J92") (pin "P$12") (pinfunction "P$12_P$12") (pintype "bidirectional"))
      (node (ref "J94") (pin "P$2") (pinfunction "P$2_P$2") (pintype "bidirectional"))
    )
    (net (code "37") (name "N$14") (class "Default")
      (node (ref "J65") (pin "P$1") (pinfunction "P$1_P$1") (pintype "bidirectional"))
    )
    (net (code "38") (name "N$15") (class "Default")
      (node (ref "J64") (pin "P$1") (pinfunction "P$1_P$1") (pintype "bidirectional"))
    )
    (net (code "39") (name "N$66") (class "Default")
      (node (ref "J60") (pin "P$1") (pinfunction "P$1_P$1") (pintype "bidirectional"))
    )
    (net (code "40") (name "N$67") (class "Default")
      (node (ref "J58") (pin "P$1") (pinfunction "P$1_P$1") (pintype "bidirectional"))
    )
    (net (code "41") (name "Net-(C15-Pad1)") (class "Default")
      (node (ref "C15") (pin "1") (pinfunction "1_1") (pintype "passive"))
      (node (ref "R12") (pin "1") (pinfunction "1_1") (pintype "passive"))
    )
    (net (code "42") (name "Net-(C16-Pad1)") (class "Default")
      (node (ref "C16") (pin "1") (pinfunction "1_1") (pintype "passive"))
      (node (ref "J38") (pin "P$1") (pinfunction "P$1_P$1") (pintype "bidirectional"))
      (node (ref "U6") (pin "14") (pinfunction "VS_14") (pintype "bidirectional"))
      (node (ref "U6") (pin "15") (pinfunction "VS_15") (pintype "bidirectional"))
    )
    (net (code "43") (name "Net-(D2-C)") (class "Default")
      (node (ref "D1") (pin "A") (pinfunction "A_A") (pintype "passive"))
      (node (ref "D2") (pin "A") (pinfunction "C_A") (pintype "passive"))
      (node (ref "R18") (pin "1") (pinfunction "1_1") (pintype "passive"))
    )
    (net (code "44") (name "Net-(D3-PadA)") (class "Default")
      (node (ref "D3") (pin "A") (pinfunction "A_A") (pintype "passive"))
      (node (ref "R19") (pin "1") (pinfunction "1_1") (pintype "passive"))
    )
    (net (code "45") (name "Net-(J4-P$3)") (class "Default")
      (node (ref "J4") (pin "P$1") (pinfunction "P$3_P$1") (pintype "bidirectional"))
      (node (ref "R1") (pin "2") (pinfunction "2_2") (pintype "passive"))
      (node (ref "U1") (pin "7") (pinfunction "RON_7") (pintype "bidirectional"))
    )
    (net (code "46") (name "Net-(J6-P$3)") (class "Default")
      (node (ref "J6") (pin "P$1") (pinfunction "P$3_P$1") (pintype "bidirectional"))
      (node (ref "J7") (pin "P$1") (pinfunction "P$3_P$1") (pintype "bidirectional"))
      (node (ref "R2") (pin "1") (pinfunction "1_1") (pintype "passive"))
      (node (ref "R4") (pin "2") (pinfunction "2_2") (pintype "passive"))
      (node (ref "U1") (pin "4") (pinfunction "FB_4") (pintype "bidirectional"))
    )
    (net (code "47") (name "Net-(J8-P$3)") (class "Default")
      (node (ref "J8") (pin "P$1") (pinfunction "P$3_P$1") (pintype "bidirectional"))
      (node (ref "R5") (pin "1") (pinfunction "1_1") (pintype "passive"))
      (node (ref "U1") (pin "8") (pinfunction "ILIM_8") (pintype "bidirectional"))
    )
    (net (code "48") (name "Net-(J10-P$3)") (class "Default")
      (node (ref "C12") (pin "+") (pinfunction "+_+") (pintype "passive"))
      (node (ref "C14") (pin "+") (pinfunction "+_+") (pintype "passive"))
      (node (ref "J10") (pin "P$1") (pinfunction "P$3_P$1") (pintype "bidirectional"))
      (node (ref "J31") (pin "P$2") (pinfunction "P$2_P$2") (pintype "bidirectional"))
      (node (ref "J32") (pin "P$2") (pinfunction "P$2_P$2") (pintype "bidirectional"))
      (node (ref "J33") (pin "P$2") (pinfunction "P$2_P$2") (pintype "bidirectional"))
      (node (ref "L1") (pin "2") (pinfunction "P$2_2") (pintype "bidirectional"))
      (node (ref "R4") (pin "1") (pinfunction "1_1") (pintype "passive"))
    )
    (net (code "49") (name "Net-(J11-P$3)") (class "Default")
      (node (ref "C5") (pin "1") (pinfunction "1_1") (pintype "passive"))
      (node (ref "J11") (pin "P$1") (pinfunction "P$3_P$1") (pintype "bidirectional"))
      (node (ref "J13") (pin "P$1") (pinfunction "P$3_P$1") (pintype "bidirectional"))
      (node (ref "L1") (pin "1") (pinfunction "P$1_1") (pintype "bidirectional"))
      (node (ref "Q1") (pin "5") (pinfunction "DA_5") (pintype "bidirectional"))
      (node (ref "Q1") (pin "6") (pinfunction "DB_6") (pintype "bidirectional"))
      (node (ref "Q1") (pin "7") (pinfunction "DC_7") (pintype "bidirectional"))
      (node (ref "Q1") (pin "8") (pinfunction "DD_8") (pintype "bidirectional"))
      (node (ref "Q2") (pin "1") (pinfunction "SA_1") (pintype "bidirectional"))
      (node (ref "Q2") (pin "2") (pinfunction "SB_2") (pintype "bidirectional"))
      (node (ref "Q2") (pin "3") (pinfunction "SC_3") (pintype "bidirectional"))
      (node (ref "R5") (pin "2") (pinfunction "2_2") (pintype "passive"))
      (node (ref "U1") (pin "10") (pinfunction "SW_10") (pintype "bidirectional"))
    )
    (net (code "50") (name "Net-(J25-PadP$1)") (class "Default")
      (node (ref "J25") (pin "P$1") (pinfunction "P$1_P$1") (pintype "bidirectional"))
      (node (ref "J30") (pin "RFBIAS") (pinfunction "RFBIAS_RFBIAS") (pintype "bidirectional"))
    )
    (net (code "51") (name "Net-(J26-PadP$1)") (class "Default")
      (node (ref "J26") (pin "P$1") (pinfunction "P$1_P$1") (pintype "bidirectional"))
      (node (ref "J30") (pin "SRX") (pinfunction "SRX_SRX") (pintype "bidirectional"))
    )
    (net (code "52") (name "Net-(J27-PadP$1)") (class "Default")
      (node (ref "J27") (pin "P$1") (pinfunction "P$1_P$1") (pintype "bidirectional"))
      (node (ref "J30") (pin "STX") (pinfunction "STX_STX") (pintype "bidirectional"))
    )
    (net (code "53") (name "Net-(J28-PadP$1)") (class "Default")
      (node (ref "J28") (pin "P$1") (pinfunction "P$1_P$1") (pintype "bidirectional"))
      (node (ref "J30") (pin "GND") (pinfunction "GND_GND") (pintype "bidirectional"))
    )
    (net (code "54") (name "Net-(J29-PadP$1)") (class "Default")
      (node (ref "J29") (pin "P$1") (pinfunction "P$1_P$1") (pintype "bidirectional"))
      (node (ref "J30") (pin "BACKUPPWR") (pinfunction "BACKUPPWR_BACKUPPWR") (pintype "bidirectional"))
      (node (ref "J30") (pin "PWR") (pinfunction "PWR_PWR") (pintype "bidirectional"))
    )
    (net (code "55") (name "Net-(J34A-P$1)") (class "Default")
      (node (ref "J34") (pin "!RESET") (pinfunction "P$1_!RESET") (pintype "bidirectional"))
      (node (ref "J37") (pin "P$1") (pinfunction "P$1_P$1") (pintype "bidirectional"))
      (node (ref "S2") (pin "P$2") (pinfunction "S_P$2") (pintype "passive"))
    )
    (net (code "56") (name "Net-(J34A-P$2)") (class "Default")
      (node (ref "J34") (pin "PE_0") (pinfunction "P$2_PE_0") (pintype "bidirectional"))
      (node (ref "J37") (pin "P$2") (pinfunction "P$2_P$2") (pintype "bidirectional"))
    )
    (net (code "57") (name "Net-(J34A-P$3)") (class "Default")
      (node (ref "J34") (pin "PE_1") (pinfunction "P$3_PE_1") (pintype "bidirectional"))
      (node (ref "J37") (pin "P$3") (pinfunction "P$3_P$3") (pintype "bidirectional"))
    )
    (net (code "58") (name "Net-(J34A-P$4)") (class "Default")
      (node (ref "J34") (pin "PE_2") (pinfunction "P$4_PE_2") (pintype "bidirectional"))
      (node (ref "J37") (pin "P$4") (pinfunction "P$4_P$4") (pintype "bidirectional"))
    )
    (net (code "59") (name "Net-(J34A-P$5)") (class "Default")
      (node (ref "J34") (pin "PE_3") (pinfunction "P$5_PE_3") (pintype "bidirectional"))
      (node (ref "J37") (pin "P$5") (pinfunction "P$5_P$5") (pintype "bidirectional"))
    )
    (net (code "60") (name "Net-(J34A-P$6)") (class "Default")
      (node (ref "J34") (pin "PE_4") (pinfunction "P$6_PE_4") (pintype "bidirectional"))
      (node (ref "J37") (pin "P$6") (pinfunction "P$6_P$6") (pintype "bidirectional"))
    )
    (net (code "61") (name "Net-(J34A-P$7)") (class "Default")
      (node (ref "J34") (pin "DAC") (pinfunction "P$7_DAC") (pintype "bidirectional"))
      (node (ref "J37") (pin "P$7") (pinfunction "P$7_P$7") (pintype "bidirectional"))
    )
    (net (code "62") (name "Net-(J34A-P$11)") (class "Default")
      (node (ref "J34") (pin "UART1_RX_LED") (pinfunction "P$11_UART1_RX_LED") (pintype "bidirectional"))
      (node (ref "J37") (pin "P$11") (pinfunction "P$11_P$11") (pintype "bidirectional"))
    )
    (net (code "63") (name "Net-(J34A-P$12)") (class "Default")
      (node (ref "J34") (pin "UART1_TX_LED") (pinfunction "P$12_UART1_TX_LED") (pintype "bidirectional"))
      (node (ref "J37") (pin "P$12") (pinfunction "P$12_P$12") (pintype "bidirectional"))
    )
    (net (code "64") (name "Net-(J34A-P$15)") (class "Default")
      (node (ref "J34") (pin "UART0_RX_LED") (pinfunction "P$15_UART0_RX_LED") (pintype "bidirectional"))
      (node (ref "J37") (pin "P$15") (pinfunction "P$15_P$15") (pintype "bidirectional"))
    )
    (net (code "65") (name "Net-(J34A-P$16)") (class "Default")
      (node (ref "J34") (pin "UART0_TX_LED") (pinfunction "P$16_UART0_TX_LED") (pintype "bidirectional"))
      (node (ref "J37") (pin "P$16") (pinfunction "P$16_P$16") (pintype "bidirectional"))
    )
    (net (code "66") (name "Net-(J34A-P$19)") (class "Default")
      (node (ref "J34") (pin "T0") (pinfunction "P$19_T0") (pintype "bidirectional"))
      (node (ref "J37") (pin "P$19") (pinfunction "P$19_P$19") (pintype "bidirectional"))
    )
    (net (code "67") (name "Net-(J34A-P$20)") (class "Default")
      (node (ref "J34") (pin "T1") (pinfunction "P$20_T1") (pintype "bidirectional"))
      (node (ref "J37") (pin "P$20") (pinfunction "P$20_P$20") (pintype "bidirectional"))
    )
    (net (code "68") (name "Net-(J34B-P$13)") (class "Default")
      (node (ref "D3") (pin "C") (pinfunction "C_C") (pintype "passive"))
      (node (ref "J34") (pin "WATCHDOG") (pinfunction "P$13_WATCHDOG") (pintype "bidirectional"))
      (node (ref "J61") (pin "P$13") (pinfunction "P$13_P$13") (pintype "bidirectional"))
    )
    (net (code "69") (name "Net-(J34B-P$16)") (class "Default")
      (node (ref "J34") (pin "VUNREGULATED") (pinfunction "P$16_VUNREGULATED") (pintype "bidirectional"))
      (node (ref "J61") (pin "P$16") (pinfunction "P$16_P$16") (pintype "bidirectional"))
    )
    (net (code "70") (name "Net-(J34B-P$17)") (class "Default")
      (node (ref "J34") (pin "VTRANSPORT") (pinfunction "P$17_VTRANSPORT") (pintype "bidirectional"))
      (node (ref "J61") (pin "P$17") (pinfunction "P$17_P$17") (pintype "bidirectional"))
    )
    (net (code "71") (name "Net-(J36-Pad1)") (class "Default")
      (node (ref "J36") (pin "1") (pinfunction "1_1") (pintype "bidirectional"))
      (node (ref "J96") (pin "P$1") (pinfunction "P$1_P$1") (pintype "bidirectional"))
    )
    (net (code "72") (name "Net-(J36-Pad2)") (class "Default")
      (node (ref "J36") (pin "2") (pinfunction "2_2") (pintype "bidirectional"))
      (node (ref "J93") (pin "P$1") (pinfunction "P$1_P$1") (pintype "bidirectional"))
    )
    (net (code "73") (name "Net-(J36-Pad3)") (class "Default")
      (node (ref "J36") (pin "3") (pinfunction "3_3") (pintype "bidirectional"))
      (node (ref "J89") (pin "P$1") (pinfunction "P$1_P$1") (pintype "bidirectional"))
    )
    (net (code "74") (name "Net-(J36-Pad4)") (class "Default")
      (node (ref "J36") (pin "4") (pinfunction "4_4") (pintype "bidirectional"))
      (node (ref "J86") (pin "P$1") (pinfunction "P$1_P$1") (pintype "bidirectional"))
    )
    (net (code "75") (name "Net-(J36-Pad5)") (class "Default")
      (node (ref "J36") (pin "5") (pinfunction "5_5") (pintype "bidirectional"))
      (node (ref "J83") (pin "P$1") (pinfunction "P$1_P$1") (pintype "bidirectional"))
    )
    (net (code "76") (name "Net-(J36-Pad6)") (class "Default")
      (node (ref "J36") (pin "6") (pinfunction "6_6") (pintype "bidirectional"))
      (node (ref "J80") (pin "P$1") (pinfunction "P$1_P$1") (pintype "bidirectional"))
    )
    (net (code "77") (name "Net-(J36-Pad7)") (class "Default")
      (node (ref "J36") (pin "7") (pinfunction "7_7") (pintype "bidirectional"))
      (node (ref "J76") (pin "P$1") (pinfunction "P$1_P$1") (pintype "bidirectional"))
    )
    (net (code "78") (name "Net-(J36-Pad8)") (class "Default")
      (node (ref "J36") (pin "8") (pinfunction "8_8") (pintype "bidirectional"))
      (node (ref "J73") (pin "P$1") (pinfunction "P$1_P$1") (pintype "bidirectional"))
    )
    (net (code "79") (name "Net-(J36-Pad9)") (class "Default")
      (node (ref "J36") (pin "9") (pinfunction "9_9") (pintype "bidirectional"))
      (node (ref "J70") (pin "P$1") (pinfunction "P$1_P$1") (pintype "bidirectional"))
    )
    (net (code "80") (name "Net-(J36-Pad10)") (class "Default")
      (node (ref "J36") (pin "10") (pinfunction "10_10") (pintype "bidirectional"))
      (node (ref "J68") (pin "P$1") (pinfunction "P$1_P$1") (pintype "bidirectional"))
    )
    (net (code "81") (name "Net-(J36-Pad11)") (class "Default")
      (node (ref "J36") (pin "11") (pinfunction "11_11") (pintype "bidirectional"))
      (node (ref "J40") (pin "P$2") (pinfunction "P$2_P$2") (pintype "bidirectional"))
    )
    (net (code "82") (name "Net-(J36-Pad12)") (class "Default")
      (node (ref "J36") (pin "12") (pinfunction "12_12") (pintype "bidirectional"))
      (node (ref "J46") (pin "P$2") (pinfunction "P$2_P$2") (pintype "bidirectional"))
    )
    (net (code "83") (name "Net-(J36-Pad13)") (class "Default")
      (node (ref "J36") (pin "13") (pinfunction "13_13") (pintype "bidirectional"))
      (node (ref "J48") (pin "P$2") (pinfunction "P$2_P$2") (pintype "bidirectional"))
    )
    (net (code "84") (name "Net-(J36-Pad14)") (class "Default")
      (node (ref "J36") (pin "14") (pinfunction "14_14") (pintype "bidirectional"))
      (node (ref "J52") (pin "P$2") (pinfunction "P$2_P$2") (pintype "bidirectional"))
    )
    (net (code "85") (name "Net-(J36-Pad15)") (class "Default")
      (node (ref "J36") (pin "15") (pinfunction "15_15") (pintype "bidirectional"))
      (node (ref "J58") (pin "P$2") (pinfunction "P$2_P$2") (pintype "bidirectional"))
    )
    (net (code "86") (name "Net-(J36-Pad16)") (class "Default")
      (node (ref "J36") (pin "16") (pinfunction "16_16") (pintype "bidirectional"))
      (node (ref "J60") (pin "P$2") (pinfunction "P$2_P$2") (pintype "bidirectional"))
    )
    (net (code "87") (name "Net-(J36-Pad17)") (class "Default")
      (node (ref "J36") (pin "17") (pinfunction "17_17") (pintype "bidirectional"))
      (node (ref "J64") (pin "P$2") (pinfunction "P$2_P$2") (pintype "bidirectional"))
    )
    (net (code "88") (name "Net-(J36-Pad18)") (class "Default")
      (node (ref "J36") (pin "18") (pinfunction "18_18") (pintype "bidirectional"))
      (node (ref "J65") (pin "P$2") (pinfunction "P$2_P$2") (pintype "bidirectional"))
    )
    (net (code "89") (name "Net-(J36-Pad19)") (class "Default")
      (node (ref "J36") (pin "19") (pinfunction "19_19") (pintype "bidirectional"))
      (node (ref "J66") (pin "P$2") (pinfunction "P$2_P$2") (pintype "bidirectional"))
    )
    (net (code "90") (name "Net-(J36-Pad20)") (class "Default")
      (node (ref "J36") (pin "20") (pinfunction "20_20") (pintype "bidirectional"))
      (node (ref "J67") (pin "P$2") (pinfunction "P$2_P$2") (pintype "bidirectional"))
    )
    (net (code "91") (name "Net-(J39-P$3)") (class "Default")
      (node (ref "J39") (pin "P$1") (pinfunction "P$3_P$1") (pintype "bidirectional"))
      (node (ref "U5") (pin "7") (pinfunction "INT_7") (pintype "bidirectional"))
    )
    (net (code "92") (name "Net-(J41-PadP$1)") (class "Default")
      (node (ref "J41") (pin "P$1") (pinfunction "P$1_P$1") (pintype "bidirectional"))
      (node (ref "U7") (pin "MODE") (pinfunction "MODE_MODE") (pintype "bidirectional"))
    )
    (net (code "93") (name "Net-(J45-P$3)") (class "Default")
      (node (ref "J45") (pin "P$1") (pinfunction "P$3_P$1") (pintype "bidirectional"))
      (node (ref "U5") (pin "6") (pinfunction "DRDY/INT2_6") (pintype "bidirectional"))
    )
    (net (code "94") (name "Net-(J47-PadP$1)") (class "Default")
      (node (ref "J47") (pin "P$1") (pinfunction "P$1_P$1") (pintype "bidirectional"))
      (node (ref "U7") (pin "RX") (pinfunction "RX_RX") (pintype "bidirectional"))
    )
    (net (code "95") (name "Net-(J49-PadP$1)") (class "Default")
      (node (ref "J49") (pin "P$1") (pinfunction "P$1_P$1") (pintype "bidirectional"))
      (node (ref "U7") (pin "TX") (pinfunction "TX_TX") (pintype "bidirectional"))
    )
    (net (code "96") (name "Net-(J53-PadP$1)") (class "Default")
      (node (ref "J53") (pin "P$1") (pinfunction "P$1_P$1") (pintype "bidirectional"))
      (node (ref "U7") (pin "3.3V") (pinfunction "3.3V_3.3V") (pintype "bidirectional"))
    )
    (net (code "97") (name "Net-(J54-P$3)") (class "Default")
      (node (ref "J54") (pin "P$1") (pinfunction "P$3_P$1") (pintype "bidirectional"))
      (node (ref "J59") (pin "P$1") (pinfunction "P$3_P$1") (pintype "bidirectional"))
      (node (ref "R15") (pin "2") (pinfunction "2_2") (pintype "passive"))
      (node (ref "U8") (pin "1") (pinfunction "OUT_1") (pintype "bidirectional"))
    )
    (net (code "98") (name "Net-(Q1-G)") (class "Default")
      (node (ref "Q1") (pin "4") (pinfunction "G_4") (pintype "bidirectional"))
      (node (ref "U1") (pin "13") (pinfunction "LG_13") (pintype "bidirectional"))
    )
    (net (code "99") (name "Net-(Q1-SA)") (class "Default")
      (node (ref "Q1") (pin "1") (pinfunction "SA_1") (pintype "bidirectional"))
      (node (ref "Q1") (pin "2") (pinfunction "SB_2") (pintype "bidirectional"))
      (node (ref "Q1") (pin "3") (pinfunction "SC_3") (pintype "bidirectional"))
      (node (ref "U1") (pin "14") (pinfunction "PGND_14") (pintype "bidirectional"))
      (node (ref "U1") (pin "5") (pinfunction "SGND_5") (pintype "bidirectional"))
      (node (ref "U1") (pin "9") (pinfunction "SGND_9") (pintype "bidirectional"))
      (node (ref "U1") (pin "PAD") (pinfunction "EP_PAD") (pintype "bidirectional"))
    )
    (net (code "100") (name "Net-(Q2-G)") (class "Default")
      (node (ref "Q2") (pin "4") (pinfunction "G_4") (pintype "bidirectional"))
      (node (ref "U1") (pin "11") (pinfunction "HG_11") (pintype "bidirectional"))
    )
    (net (code "101") (name "Net-(Q3-PadG)") (class "Default")
      (node (ref "Q3") (pin "G") (pinfunction "G_G") (pintype "bidirectional"))
      (node (ref "R3") (pin "1") (pinfunction "1_1") (pintype "passive"))
    )
    (net (code "102") (name "Net-(R23-1)") (class "Default")
      (node (ref "R23") (pin "P$1") (pinfunction "1_P$1") (pintype "passive"))
      (node (ref "U10") (pin "4") (pinfunction "P0_4") (pintype "bidirectional"))
    )
    (net (code "103") (name "Net-(R23-2)") (class "Default")
      (node (ref "D4") (pin "C") (pinfunction "C_C") (pintype "passive"))
      (node (ref "R23") (pin "P$2") (pinfunction "2_P$2") (pintype "passive"))
    )
    (net (code "104") (name "Net-(R24-1)") (class "Default")
      (node (ref "R24") (pin "P$1") (pinfunction "1_P$1") (pintype "passive"))
      (node (ref "U10") (pin "5") (pinfunction "P1_5") (pintype "bidirectional"))
    )
    (net (code "105") (name "Net-(R24-2)") (class "Default")
      (node (ref "D5") (pin "C") (pinfunction "C_C") (pintype "passive"))
      (node (ref "R24") (pin "P$2") (pinfunction "2_P$2") (pintype "passive"))
    )
    (net (code "106") (name "Net-(R25-1)") (class "Default")
      (node (ref "R25") (pin "P$1") (pinfunction "1_P$1") (pintype "passive"))
      (node (ref "U10") (pin "6") (pinfunction "P2_6") (pintype "bidirectional"))
    )
    (net (code "107") (name "Net-(R25-2)") (class "Default")
      (node (ref "D6") (pin "C") (pinfunction "C_C") (pintype "passive"))
      (node (ref "R25") (pin "P$2") (pinfunction "2_P$2") (pintype "passive"))
    )
    (net (code "108") (name "Net-(R26-1)") (class "Default")
      (node (ref "R26") (pin "P$1") (pinfunction "1_P$1") (pintype "passive"))
      (node (ref "U10") (pin "7") (pinfunction "P3_7") (pintype "bidirectional"))
    )
    (net (code "109") (name "Net-(R26-2)") (class "Default")
      (node (ref "D7") (pin "C") (pinfunction "C_C") (pintype "passive"))
      (node (ref "R26") (pin "P$2") (pinfunction "2_P$2") (pintype "passive"))
    )
    (net (code "110") (name "Net-(R27-1)") (class "Default")
      (node (ref "R27") (pin "P$1") (pinfunction "1_P$1") (pintype "passive"))
      (node (ref "U10") (pin "12") (pinfunction "P7_12") (pintype "bidirectional"))
    )
    (net (code "111") (name "Net-(R27-2)") (class "Default")
      (node (ref "D8") (pin "C") (pinfunction "C_C") (pintype "passive"))
      (node (ref "R27") (pin "P$2") (pinfunction "2_P$2") (pintype "passive"))
    )
    (net (code "112") (name "Net-(R28-1)") (class "Default")
      (node (ref "R28") (pin "P$1") (pinfunction "1_P$1") (pintype "passive"))
      (node (ref "U10") (pin "11") (pinfunction "P6_11") (pintype "bidirectional"))
    )
    (net (code "113") (name "Net-(R28-2)") (class "Default")
      (node (ref "D9") (pin "C") (pinfunction "C_C") (pintype "passive"))
      (node (ref "R28") (pin "P$2") (pinfunction "2_P$2") (pintype "passive"))
    )
    (net (code "114") (name "Net-(R29-1)") (class "Default")
      (node (ref "R29") (pin "P$1") (pinfunction "1_P$1") (pintype "passive"))
      (node (ref "U10") (pin "10") (pinfunction "P5_10") (pintype "bidirectional"))
    )
    (net (code "115") (name "Net-(R29-2)") (class "Default")
      (node (ref "D10") (pin "C") (pinfunction "C_C") (pintype "passive"))
      (node (ref "R29") (pin "P$2") (pinfunction "2_P$2") (pintype "passive"))
    )
    (net (code "116") (name "Net-(R30-1)") (class "Default")
      (node (ref "R30") (pin "P$1") (pinfunction "1_P$1") (pintype "passive"))
      (node (ref "U10") (pin "9") (pinfunction "P4_9") (pintype "bidirectional"))
    )
    (net (code "117") (name "Net-(R30-2)") (class "Default")
      (node (ref "D11") (pin "C") (pinfunction "C_C") (pintype "passive"))
      (node (ref "R30") (pin "P$2") (pinfunction "2_P$2") (pintype "passive"))
    )
    (net (code "118") (name "Net-(S1-1)") (class "Default")
      (node (ref "S1") (pin "2") (pinfunction "1_2") (pintype "bidirectional"))
      (node (ref "U1") (pin "3") (pinfunction "EN_3") (pintype "bidirectional"))
    )
    (net (code "119") (name "Net-(S3-1)") (class "Default")
      (node (ref "S3") (pin "2") (pinfunction "1_2") (pintype "bidirectional"))
      (node (ref "U13") (pin "1") (pinfunction "I0_1") (pintype "input"))
    )
    (net (code "120") (name "Net-(U1-BST)") (class "Default")
      (node (ref "C5") (pin "2") (pinfunction "2_2") (pintype "passive"))
      (node (ref "U1") (pin "12") (pinfunction "BST_12") (pintype "bidirectional"))
    )
    (net (code "121") (name "Net-(U1-SS)") (class "Default")
      (node (ref "C1") (pin "1") (pinfunction "1_1") (pintype "passive"))
      (node (ref "U1") (pin "6") (pinfunction "SS_6") (pintype "bidirectional"))
    )
    (net (code "122") (name "Net-(U1-VCC)") (class "Default")
      (node (ref "C2") (pin "+") (pinfunction "+_+") (pintype "passive"))
      (node (ref "C3") (pin "+") (pinfunction "+_+") (pintype "passive"))
      (node (ref "U1") (pin "1") (pinfunction "VCC_1") (pintype "bidirectional"))
    )
    (net (code "123") (name "Net-(U2-ADJ{slash}GND)") (class "Default")
      (node (ref "R6") (pin "2") (pinfunction "2_2") (pintype "passive"))
      (node (ref "R7") (pin "1") (pinfunction "1_1") (pintype "passive"))
      (node (ref "U2") (pin "1") (pinfunction "ADJ/GND_1") (pintype "bidirectional"))
    )
    (net (code "124") (name "Net-(U2-OUTPUT)") (class "Default")
      (node (ref "C4") (pin "+") (pinfunction "+_+") (pintype "passive"))
      (node (ref "J15") (pin "P$2") (pinfunction "P$2_P$2") (pintype "bidirectional"))
      (node (ref "R7") (pin "2") (pinfunction "2_2") (pintype "passive"))
      (node (ref "U2") (pin "2") (pinfunction "OUTPUT_2") (pintype "bidirectional"))
      (node (ref "U2") (pin "TAB") (pinfunction "VOUT_TAB") (pintype "bidirectional"))
    )
    (net (code "125") (name "Net-(U3-ADJ{slash}GND)") (class "Default")
      (node (ref "R8") (pin "1") (pinfunction "1_1") (pintype "passive"))
      (node (ref "R9") (pin "2") (pinfunction "2_2") (pintype "passive"))
      (node (ref "U3") (pin "1") (pinfunction "ADJ/GND_1") (pintype "bidirectional"))
    )
    (net (code "126") (name "Net-(U3-OUTPUT)") (class "Default")
      (node (ref "C7") (pin "+") (pinfunction "+_+") (pintype "passive"))
      (node (ref "J20") (pin "P$2") (pinfunction "P$2_P$2") (pintype "bidirectional"))
      (node (ref "R8") (pin "2") (pinfunction "2_2") (pintype "passive"))
      (node (ref "U3") (pin "2") (pinfunction "OUTPUT_2") (pintype "bidirectional"))
      (node (ref "U3") (pin "TAB") (pinfunction "VOUT_TAB") (pintype "bidirectional"))
    )
    (net (code "127") (name "Net-(U4-ADJ{slash}GND)") (class "Default")
      (node (ref "R10") (pin "1") (pinfunction "1_1") (pintype "passive"))
      (node (ref "R11") (pin "2") (pinfunction "2_2") (pintype "passive"))
      (node (ref "U4") (pin "1") (pinfunction "ADJ/GND_1") (pintype "bidirectional"))
    )
    (net (code "128") (name "Net-(U4-OUTPUT)") (class "Default")
      (node (ref "C11") (pin "+") (pinfunction "+_+") (pintype "passive"))
      (node (ref "J23") (pin "P$2") (pinfunction "P$2_P$2") (pintype "bidirectional"))
      (node (ref "R10") (pin "2") (pinfunction "2_2") (pintype "passive"))
      (node (ref "U4") (pin "2") (pinfunction "OUTPUT_2") (pintype "bidirectional"))
      (node (ref "U4") (pin "TAB") (pinfunction "VOUT_TAB") (pintype "bidirectional"))
    )
    (net (code "129") (name "Net-(U5-CS)") (class "Default")
      (node (ref "R14") (pin "1") (pinfunction "1_1") (pintype "passive"))
      (node (ref "U5") (pin "5") (pinfunction "CS_5") (pintype "bidirectional"))
    )
    (net (code "130") (name "Net-(U5-PLLFILT)") (class "Default")
      (node (ref "C15") (pin "2") (pinfunction "2_2") (pintype "passive"))
      (node (ref "C17") (pin "1") (pinfunction "1_1") (pintype "passive"))
      (node (ref "U5") (pin "14") (pinfunction "PLLFILT_14") (pintype "bidirectional"))
    )
    (net (code "131") (name "Net-(U5-VDD)") (class "Default")
      (node (ref "C18") (pin "1") (pinfunction "1_1") (pintype "passive"))
      (node (ref "C22") (pin "+") (pinfunction "+_+") (pintype "passive"))
      (node (ref "J50") (pin "P$1") (pinfunction "P$1_P$1") (pintype "bidirectional"))
      (node (ref "U5") (pin "1") (pinfunction "VDD_IO_1") (pintype "bidirectional"))
      (node (ref "U5") (pin "16") (pinfunction "VDD_16") (pintype "bidirectional"))
    )
    (net (code "132") (name "Net-(U6-XOUT)") (class "Default")
      (node (ref "C21") (pin "1") (pinfunction "1_1") (pintype "passive"))
      (node (ref "J57") (pin "P$2") (pinfunction "P$2_P$2") (pintype "bidirectional"))
      (node (ref "U6") (pin "12") (pinfunction "XOUT_12") (pintype "bidirectional"))
    )
    (net (code "133") (name "Net-(U6-YOUT)") (class "Default")
      (node (ref "C20") (pin "1") (pinfunction "1_1") (pintype "passive"))
      (node (ref "J56") (pin "P$2") (pinfunction "P$2_P$2") (pintype "bidirectional"))
      (node (ref "U6") (pin "10") (pinfunction "YOUT_10") (pintype "bidirectional"))
    )
    (net (code "134") (name "Net-(U6-ZOUT)") (class "Default")
      (node (ref "C19") (pin "1") (pinfunction "1_1") (pintype "passive"))
      (node (ref "J55") (pin "P$2") (pinfunction "P$2_P$2") (pintype "bidirectional"))
      (node (ref "U6") (pin "8") (pinfunction "ZOUT_8") (pintype "bidirectional"))
    )
    (net (code "135") (name "Net-(U9-CH0)") (class "Default")
      (node (ref "J71") (pin "P$1") (pinfunction "P$1_P$1") (pintype "bidirectional"))
      (node (ref "U9") (pin "1") (pinfunction "CH0_1") (pintype "bidirectional"))
    )
    (net (code "136") (name "Net-(U9-CH1)") (class "Default")
      (node (ref "J74") (pin "P$1") (pinfunction "P$1_P$1") (pintype "bidirectional"))
      (node (ref "U9") (pin "2") (pinfunction "CH1_2") (pintype "bidirectional"))
    )
    (net (code "137") (name "Net-(U9-CH2)") (class "Default")
      (node (ref "J77") (pin "P$1") (pinfunction "P$1_P$1") (pintype "bidirectional"))
      (node (ref "U9") (pin "3") (pinfunction "CH2_3") (pintype "bidirectional"))
    )
    (net (code "138") (name "Net-(U9-CH3)") (class "Default")
      (node (ref "J81") (pin "P$1") (pinfunction "P$1_P$1") (pintype "bidirectional"))
      (node (ref "U9") (pin "4") (pinfunction "CH3_4") (pintype "bidirectional"))
    )
    (net (code "139") (name "Net-(U9-CH4)") (class "Default")
      (node (ref "J84") (pin "P$1") (pinfunction "P$1_P$1") (pintype "bidirectional"))
      (node (ref "U9") (pin "5") (pinfunction "CH4_5") (pintype "bidirectional"))
    )
    (net (code "140") (name "Net-(U9-CH5)") (class "Default")
      (node (ref "J87") (pin "P$1") (pinfunction "P$1_P$1") (pintype "bidirectional"))
      (node (ref "U9") (pin "6") (pinfunction "CH5_6") (pintype "bidirectional"))
    )
    (net (code "141") (name "Net-(U9-CH6)") (class "Default")
      (node (ref "J90") (pin "P$1") (pinfunction "P$1_P$1") (pintype "bidirectional"))
      (node (ref "U9") (pin "7") (pinfunction "CH6_7") (pintype "bidirectional"))
    )
    (net (code "142") (name "Net-(U9-CH7)") (class "Default")
      (node (ref "J94") (pin "P$1") (pinfunction "P$1_P$1") (pintype "bidirectional"))
      (node (ref "U9") (pin "8") (pinfunction "CH7_8") (pintype "bidirectional"))
    )
    (net (code "143") (name "Net-(U9-REF)") (class "Default")
      (node (ref "L2") (pin "1") (pinfunction "1_1") (pintype "passive"))
      (node (ref "U9") (pin "10") (pinfunction "REF_10") (pintype "bidirectional"))
    )
    (net (code "144") (name "Net-(U11A-IN)") (class "Default")
      (node (ref "R20") (pin "2") (pinfunction "2_2") (pintype "passive"))
      (node (ref "U11") (pin "3") (pinfunction "IN_3") (pintype "bidirectional"))
      (node (ref "U12") (pin "3") (pinfunction "E_3") (pintype "bidirectional"))
    )
    (net (code "145") (name "Net-(U11A-OUT)") (class "Default")
      (node (ref "Q4") (pin "G") (pinfunction "G_G") (pintype "bidirectional"))
      (node (ref "Q5") (pin "G") (pinfunction "G_G") (pintype "bidirectional"))
      (node (ref "Q6") (pin "G") (pinfunction "G_G") (pintype "bidirectional"))
      (node (ref "U11") (pin "5") (pinfunction "OUT_5") (pintype "bidirectional"))
    )
    (net (code "146") (name "Net-(U12-A)") (class "Default")
      (node (ref "R22") (pin "1") (pinfunction "1_1") (pintype "passive"))
      (node (ref "U12") (pin "1") (pinfunction "A_1") (pintype "bidirectional"))
      (node (ref "U13") (pin "4") (pinfunction "O_4") (pintype "output"))
    )
    (net (code "147") (name "Net-(U13A-I1)") (class "Default")
      (node (ref "J97") (pin "P$1") (pinfunction "P$1_P$1") (pintype "bidirectional"))
      (node (ref "R21") (pin "1") (pinfunction "1_1") (pintype "passive"))
      (node (ref "U13") (pin "2") (pinfunction "I1_2") (pintype "input"))
    )
    (net (code "148") (name "POWER_LIPO+_IN") (class "Default")
      (node (ref "J44") (pin "7@0") (pinfunction "7_7@0") (pintype "bidirectional"))
      (node (ref "J44") (pin "7@1") (pinfunction "7_7@1") (pintype "bidirectional"))
      (node (ref "J44") (pin "7@2") (pinfunction "7_7@2") (pintype "bidirectional"))
      (node (ref "J44") (pin "7@3") (pinfunction "7_7@3") (pintype "bidirectional"))
      (node (ref "J44") (pin "7@4") (pinfunction "7_7@4") (pintype "bidirectional"))
      (node (ref "J44") (pin "7@5") (pinfunction "7_7@5") (pintype "bidirectional"))
      (node (ref "Q3") (pin "D") (pinfunction "D_D") (pintype "bidirectional"))
    )
    (net (code "149") (name "POWER_LIPO_POST") (class "Default")
      (node (ref "C8") (pin "+") (pinfunction "+_+") (pintype "passive"))
      (node (ref "C9") (pin "+") (pinfunction "+_+") (pintype "passive"))
      (node (ref "J5") (pin "P$1") (pinfunction "P$3_P$1") (pintype "bidirectional"))
      (node (ref "Q2") (pin "5") (pinfunction "DA_5") (pintype "bidirectional"))
      (node (ref "Q2") (pin "6") (pinfunction "DB_6") (pintype "bidirectional"))
      (node (ref "Q2") (pin "7") (pinfunction "DC_7") (pintype "bidirectional"))
      (node (ref "Q2") (pin "8") (pinfunction "DD_8") (pintype "bidirectional"))
      (node (ref "Q3") (pin "S") (pinfunction "S_S") (pintype "bidirectional"))
      (node (ref "R1") (pin "1") (pinfunction "1_1") (pintype "passive"))
      (node (ref "U1") (pin "2") (pinfunction "VIN_2") (pintype "bidirectional"))
    )
    (net (code "150") (name "QUAD0A") (class "Default")
      (node (ref "J83") (pin "P$2") (pinfunction "P$2_P$2") (pintype "bidirectional"))
    )
    (net (code "151") (name "QUAD0B") (class "Default")
      (node (ref "J80") (pin "P$2") (pinfunction "P$2_P$2") (pintype "bidirectional"))
    )
    (net (code "152") (name "QUAD1A") (class "Default")
      (node (ref "J76") (pin "P$2") (pinfunction "P$2_P$2") (pintype "bidirectional"))
    )
    (net (code "153") (name "QUAD1B") (class "Default")
      (node (ref "J73") (pin "P$2") (pinfunction "P$2_P$2") (pintype "bidirectional"))
    )
    (net (code "154") (name "SCL") (class "Default")
      (node (ref "J34") (pin "SCL") (pinfunction "P$15_SCL") (pintype "bidirectional"))
      (node (ref "J61") (pin "P$15") (pinfunction "P$15_P$15") (pintype "bidirectional"))
      (node (ref "J68") (pin "P$2") (pinfunction "P$2_P$2") (pintype "bidirectional"))
      (node (ref "J85") (pin "P$1") (pinfunction "P$3_P$1") (pintype "bidirectional"))
      (node (ref "U10") (pin "14") (pinfunction "SCL_14") (pintype "bidirectional"))
      (node (ref "U5") (pin "2") (pinfunction "SCL/SPC_2") (pintype "bidirectional"))
      (node (ref "U9") (pin "14") (pinfunction "SCL_14") (pintype "bidirectional"))
    )
    (net (code "155") (name "SDA") (class "Default")
      (node (ref "J34") (pin "SDA") (pinfunction "P$14_SDA") (pintype "bidirectional"))
      (node (ref "J61") (pin "P$14") (pinfunction "P$14_P$14") (pintype "bidirectional"))
      (node (ref "J70") (pin "P$2") (pinfunction "P$2_P$2") (pintype "bidirectional"))
      (node (ref "J88") (pin "P$1") (pinfunction "P$3_P$1") (pintype "bidirectional"))
      (node (ref "U10") (pin "15") (pinfunction "SDA_15") (pintype "bidirectional"))
      (node (ref "U5") (pin "3") (pinfunction "SDA/SDI/SDO_3") (pintype "bidirectional"))
      (node (ref "U9") (pin "15") (pinfunction "SDA_15") (pintype "bidirectional"))
    )
    (net (code "156") (name "SPM2") (class "Default")
      (node (ref "J89") (pin "P$2") (pinfunction "P$2_P$2") (pintype "bidirectional"))
    )
    (net (code "157") (name "SPWM0") (class "Default")
      (node (ref "J96") (pin "P$2") (pinfunction "P$2_P$2") (pintype "bidirectional"))
    )
    (net (code "158") (name "SPWM1") (class "Default")
      (node (ref "J93") (pin "P$2") (pinfunction "P$2_P$2") (pintype "bidirectional"))
    )
    (net (code "159") (name "SRX0") (class "Default")
      (node (ref "J27") (pin "P$2") (pinfunction "P$2_P$2") (pintype "bidirectional"))
      (node (ref "J34") (pin "UART0_RX") (pinfunction "P$17_UART0_RX") (pintype "bidirectional"))
      (node (ref "J37") (pin "P$17") (pinfunction "P$17_P$17") (pintype "bidirectional"))
    )
    (net (code "160") (name "SRX1") (class "Default")
      (node (ref "J34") (pin "UART1_RX") (pinfunction "P$13_UART1_RX") (pintype "bidirectional"))
      (node (ref "J37") (pin "P$13") (pinfunction "P$13_P$13") (pintype "bidirectional"))
      (node (ref "J49") (pin "P$2") (pinfunction "P$2_P$2") (pintype "bidirectional"))
    )
    (net (code "161") (name "STX0") (class "Default")
      (node (ref "J26") (pin "P$2") (pinfunction "P$2_P$2") (pintype "bidirectional"))
      (node (ref "J34") (pin "UART0_TX") (pinfunction "P$18_UART0_TX") (pintype "bidirectional"))
      (node (ref "J37") (pin "P$18") (pinfunction "P$18_P$18") (pintype "bidirectional"))
    )
    (net (code "162") (name "STX1") (class "Default")
      (node (ref "J34") (pin "UART1_TX") (pinfunction "P$14_UART1_TX") (pintype "bidirectional"))
      (node (ref "J37") (pin "P$14") (pinfunction "P$14_P$14") (pintype "bidirectional"))
      (node (ref "J47") (pin "P$2") (pinfunction "P$2_P$2") (pintype "bidirectional"))
    )
    (net (code "163") (name "VMOTOR_A2D") (class "Default")
      (node (ref "J62") (pin "P$1") (pinfunction "P$3_P$1") (pintype "bidirectional"))
      (node (ref "R16") (pin "1") (pinfunction "1_1") (pintype "passive"))
      (node (ref "R17") (pin "2") (pinfunction "2_2") (pintype "passive"))
    )
    (net (code "164") (name "unconnected-(J25-PadP$2)") (class "Default")
      (node (ref "J25") (pin "P$2") (pinfunction "P$2_P$2") (pintype "bidirectional"))
    )
    (net (code "165") (name "unconnected-(J69-P$3-PadP$1)") (class "Default")
      (node (ref "J69") (pin "P$1") (pinfunction "P$3_P$1") (pintype "bidirectional"))
    )
    (net (code "166") (name "unconnected-(J72-P$3-PadP$1)") (class "Default")
      (node (ref "J72") (pin "P$1") (pinfunction "P$3_P$1") (pintype "bidirectional"))
    )
    (net (code "167") (name "unconnected-(J82-P$3-PadP$1)") (class "Default")
      (node (ref "J82") (pin "P$1") (pinfunction "P$3_P$1") (pintype "bidirectional"))
    )
    (net (code "168") (name "unconnected-(J97-PadP$2)") (class "Default")
      (node (ref "J97") (pin "P$2") (pinfunction "P$2_P$2") (pintype "bidirectional"))
    )
    (net (code "169") (name "unconnected-(S1-2-Pad3)") (class "Default")
      (node (ref "S1") (pin "3") (pinfunction "2_3") (pintype "bidirectional"))
    )
    (net (code "170") (name "unconnected-(S1-Pad4)") (class "Default")
      (node (ref "S1") (pin "4") (pinfunction "4_4") (pintype "no_connect"))
    )
    (net (code "171") (name "unconnected-(S1-Pad5)") (class "Default")
      (node (ref "S1") (pin "5") (pinfunction "5_5") (pintype "no_connect"))
    )
    (net (code "172") (name "unconnected-(S3-Pad4)") (class "Default")
      (node (ref "S3") (pin "4") (pinfunction "4_4") (pintype "no_connect"))
    )
    (net (code "173") (name "unconnected-(S3-Pad5)") (class "Default")
      (node (ref "S3") (pin "5") (pinfunction "5_5") (pintype "no_connect"))
    )
    (net (code "174") (name "unconnected-(U5-SDO{slash}SA0-Pad4)") (class "Default")
      (node (ref "U5") (pin "4") (pinfunction "SDO/SA0_4") (pintype "bidirectional"))
    )
    (net (code "175") (name "unconnected-(U6-ST-Pad2)") (class "Default")
      (node (ref "U6") (pin "2") (pinfunction "ST_2") (pintype "bidirectional"))
    )
    (net (code "176") (name "unconnected-(U10A-~{INT}-Pad13)") (class "Default")
      (node (ref "U10") (pin "13") (pinfunction "~{INT}_13") (pintype "bidirectional"))
    )
  )
)
